# Digital_In-Out.net
KiCad netlist of a schematic drawn in Altium Designer
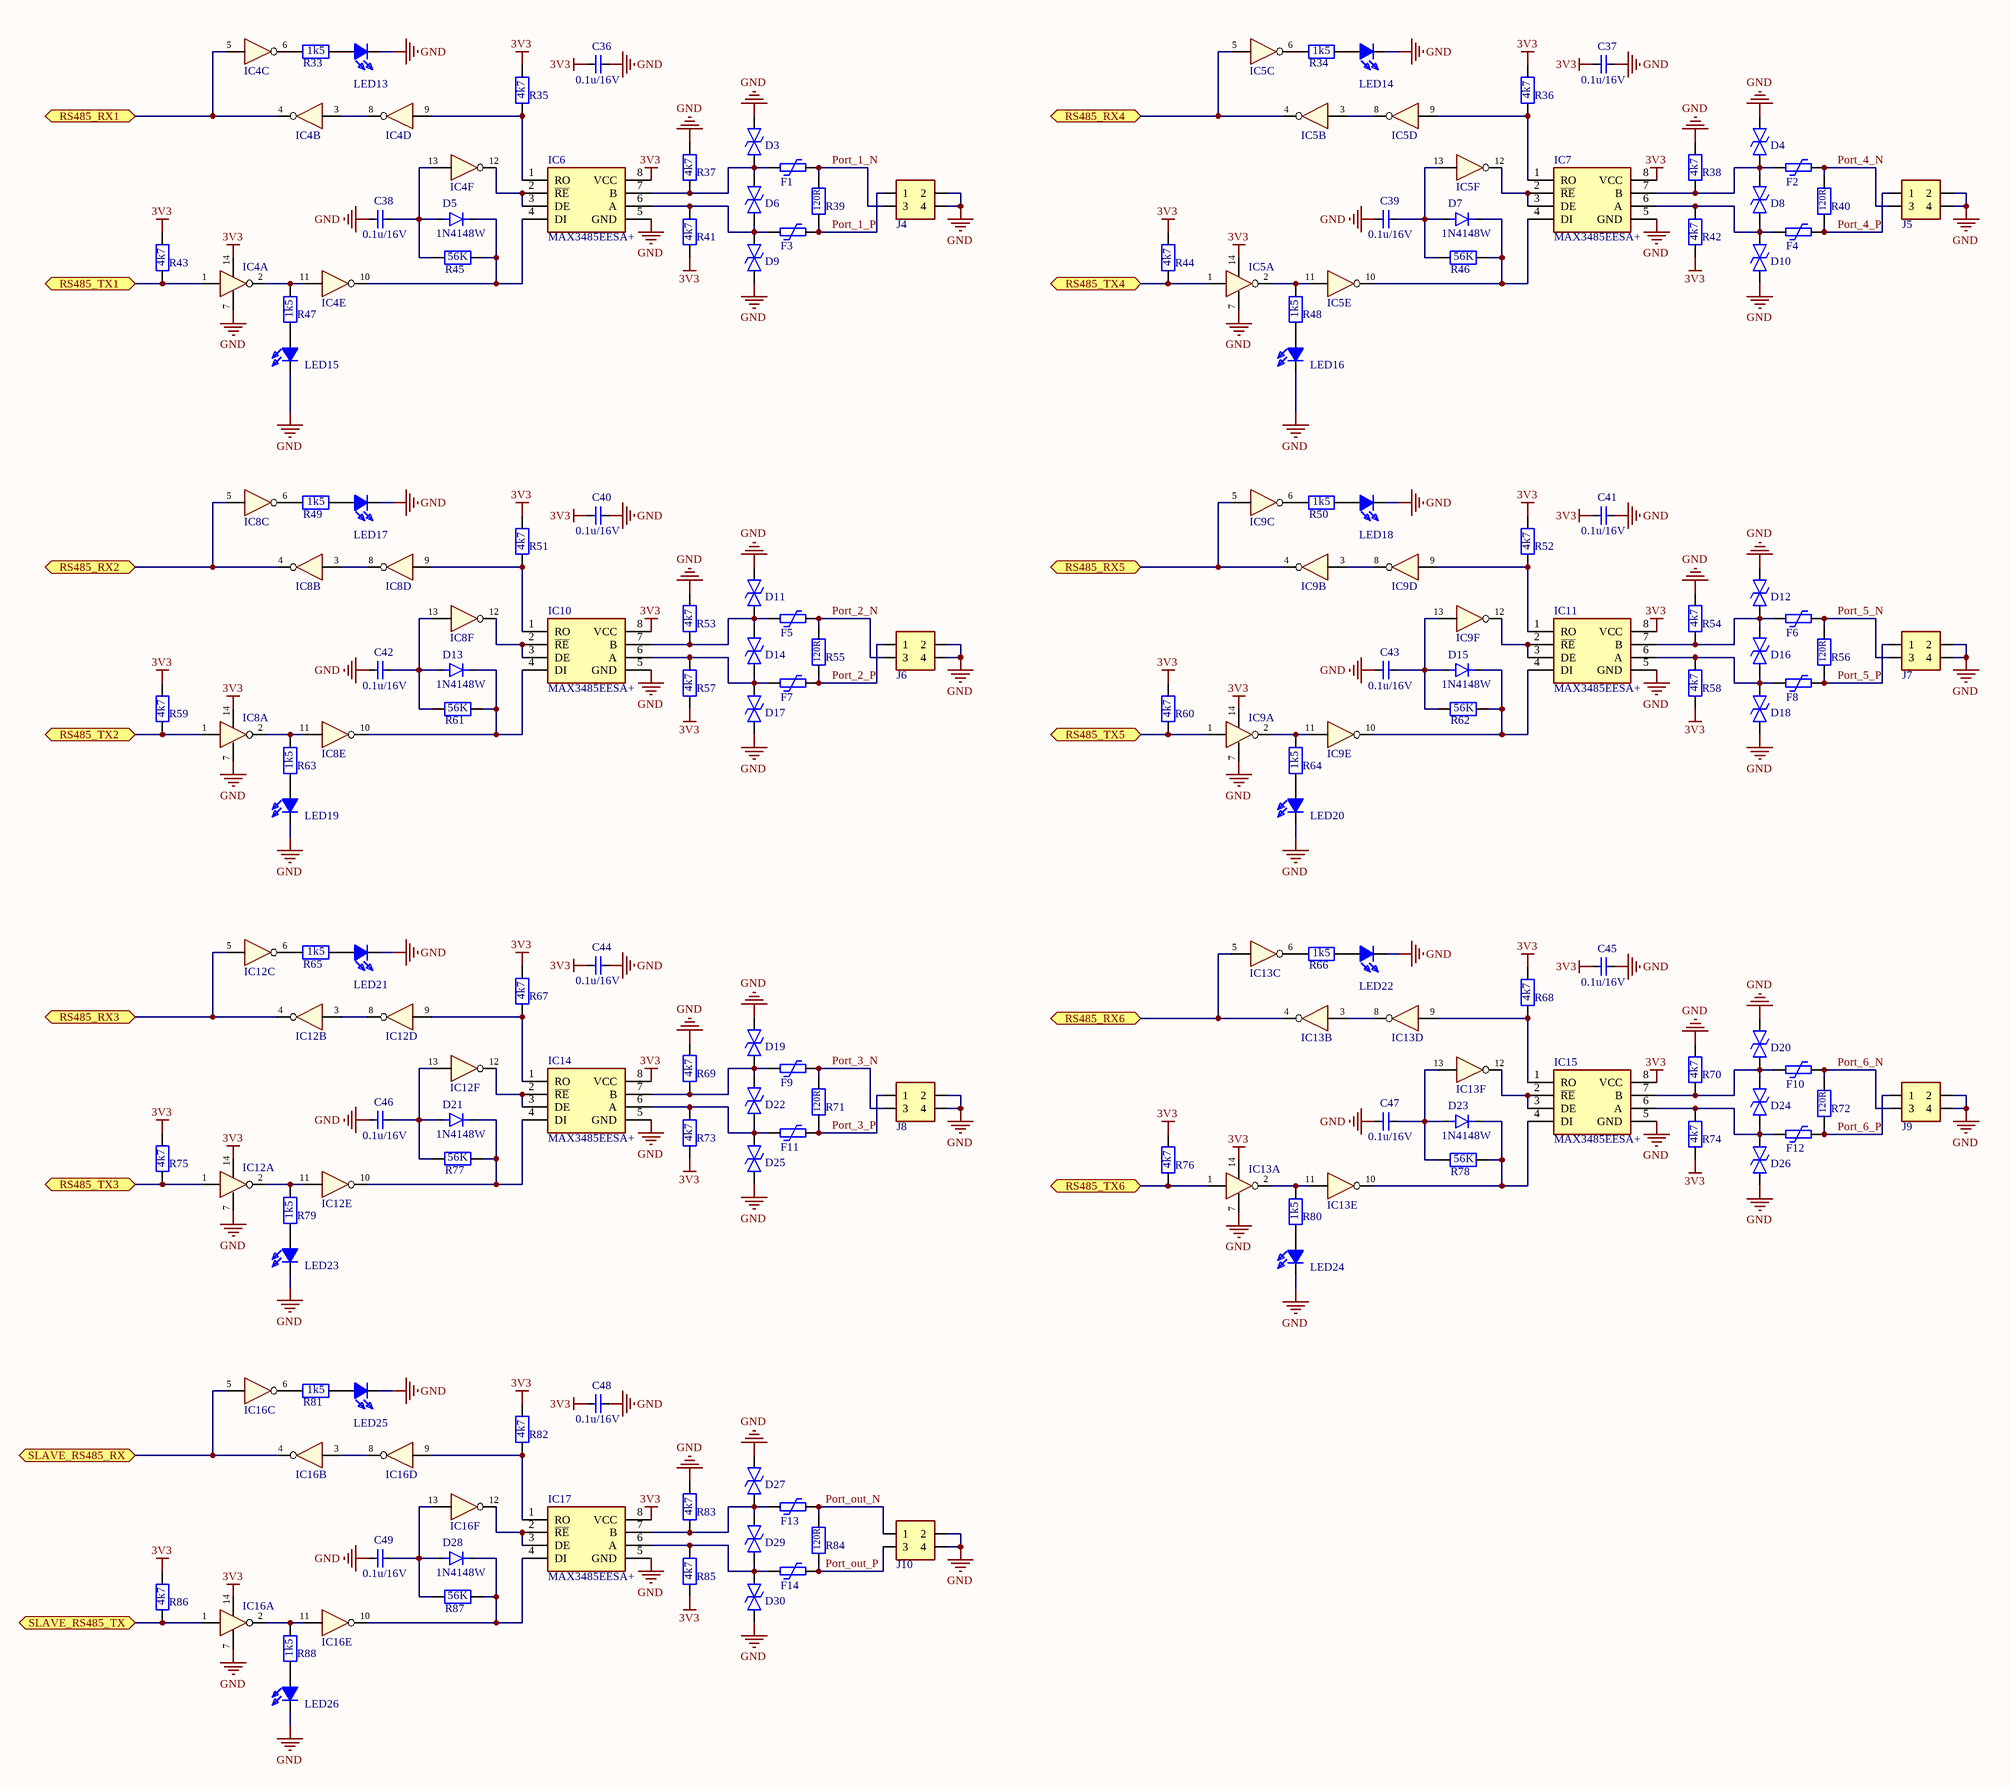
[diagram p0: Digital In-Out.SchDoc]

(export (version "E")
  (design (tool "Eeschema 10.0.6"))
  (components
    (comp (ref "C36")
      (value "0.1u/16V")
      (footprint "SamacSys:CAPC1608X95N")
      (description "Multilayer Ceramic Capacitors MLCC - SMD/SMT 16V 100pF C0G 0603 1%")
      (fields
        (field (name "MANUFACTURER_PART_NUMBER") "C0603C101F4GAC")
        (field (name "MOUSER PART NUMBER") "80-C0603C101F4G")
      )
      (libsource (lib "SamacSys") (part "Cap 0603 0.1u/16V"))
    )
    (comp (ref "C37")
      (value "0.1u/16V")
      (footprint "SamacSys:CAPC1608X95N")
      (description "Multilayer Ceramic Capacitors MLCC - SMD/SMT 16V 100pF C0G 0603 1%")
      (fields
        (field (name "MANUFACTURER_PART_NUMBER") "C0603C101F4GAC")
        (field (name "MOUSER PART NUMBER") "80-C0603C101F4G")
      )
      (libsource (lib "SamacSys") (part "Cap 0603 0.1u/16V"))
    )
    (comp (ref "C38")
      (value "0.1u/16V")
      (footprint "SamacSys:CAPC1608X95N")
      (description "Multilayer Ceramic Capacitors MLCC - SMD/SMT 16V 100pF C0G 0603 1%")
      (fields
        (field (name "MANUFACTURER_PART_NUMBER") "C0603C101F4GAC")
        (field (name "MOUSER PART NUMBER") "80-C0603C101F4G")
      )
      (libsource (lib "SamacSys") (part "Cap 0603 0.1u/16V"))
    )
    (comp (ref "C39")
      (value "0.1u/16V")
      (footprint "SamacSys:CAPC1608X95N")
      (description "Multilayer Ceramic Capacitors MLCC - SMD/SMT 16V 100pF C0G 0603 1%")
      (fields
        (field (name "MANUFACTURER_PART_NUMBER") "C0603C101F4GAC")
        (field (name "MOUSER PART NUMBER") "80-C0603C101F4G")
      )
      (libsource (lib "SamacSys") (part "Cap 0603 0.1u/16V"))
    )
    (comp (ref "C40")
      (value "0.1u/16V")
      (footprint "SamacSys:CAPC1608X95N")
      (description "Multilayer Ceramic Capacitors MLCC - SMD/SMT 16V 100pF C0G 0603 1%")
      (fields
        (field (name "MANUFACTURER_PART_NUMBER") "C0603C101F4GAC")
        (field (name "MOUSER PART NUMBER") "80-C0603C101F4G")
      )
      (libsource (lib "SamacSys") (part "Cap 0603 0.1u/16V"))
    )
    (comp (ref "C41")
      (value "0.1u/16V")
      (footprint "SamacSys:CAPC1608X95N")
      (description "Multilayer Ceramic Capacitors MLCC - SMD/SMT 16V 100pF C0G 0603 1%")
      (fields
        (field (name "MANUFACTURER_PART_NUMBER") "C0603C101F4GAC")
        (field (name "MOUSER PART NUMBER") "80-C0603C101F4G")
      )
      (libsource (lib "SamacSys") (part "Cap 0603 0.1u/16V"))
    )
    (comp (ref "C42")
      (value "0.1u/16V")
      (footprint "SamacSys:CAPC1608X95N")
      (description "Multilayer Ceramic Capacitors MLCC - SMD/SMT 16V 100pF C0G 0603 1%")
      (fields
        (field (name "MANUFACTURER_PART_NUMBER") "C0603C101F4GAC")
        (field (name "MOUSER PART NUMBER") "80-C0603C101F4G")
      )
      (libsource (lib "SamacSys") (part "Cap 0603 0.1u/16V"))
    )
    (comp (ref "C43")
      (value "0.1u/16V")
      (footprint "SamacSys:CAPC1608X95N")
      (description "Multilayer Ceramic Capacitors MLCC - SMD/SMT 16V 100pF C0G 0603 1%")
      (fields
        (field (name "MANUFACTURER_PART_NUMBER") "C0603C101F4GAC")
        (field (name "MOUSER PART NUMBER") "80-C0603C101F4G")
      )
      (libsource (lib "SamacSys") (part "Cap 0603 0.1u/16V"))
    )
    (comp (ref "C44")
      (value "0.1u/16V")
      (footprint "SamacSys:CAPC1608X95N")
      (description "Multilayer Ceramic Capacitors MLCC - SMD/SMT 16V 100pF C0G 0603 1%")
      (fields
        (field (name "MANUFACTURER_PART_NUMBER") "C0603C101F4GAC")
        (field (name "MOUSER PART NUMBER") "80-C0603C101F4G")
      )
      (libsource (lib "SamacSys") (part "Cap 0603 0.1u/16V"))
    )
    (comp (ref "C45")
      (value "0.1u/16V")
      (footprint "SamacSys:CAPC1608X95N")
      (description "Multilayer Ceramic Capacitors MLCC - SMD/SMT 16V 100pF C0G 0603 1%")
      (fields
        (field (name "MANUFACTURER_PART_NUMBER") "C0603C101F4GAC")
        (field (name "MOUSER PART NUMBER") "80-C0603C101F4G")
      )
      (libsource (lib "SamacSys") (part "Cap 0603 0.1u/16V"))
    )
    (comp (ref "C46")
      (value "0.1u/16V")
      (footprint "SamacSys:CAPC1608X95N")
      (description "Multilayer Ceramic Capacitors MLCC - SMD/SMT 16V 100pF C0G 0603 1%")
      (fields
        (field (name "MANUFACTURER_PART_NUMBER") "C0603C101F4GAC")
        (field (name "MOUSER PART NUMBER") "80-C0603C101F4G")
      )
      (libsource (lib "SamacSys") (part "Cap 0603 0.1u/16V"))
    )
    (comp (ref "C47")
      (value "0.1u/16V")
      (footprint "SamacSys:CAPC1608X95N")
      (description "Multilayer Ceramic Capacitors MLCC - SMD/SMT 16V 100pF C0G 0603 1%")
      (fields
        (field (name "MANUFACTURER_PART_NUMBER") "C0603C101F4GAC")
        (field (name "MOUSER PART NUMBER") "80-C0603C101F4G")
      )
      (libsource (lib "SamacSys") (part "Cap 0603 0.1u/16V"))
    )
    (comp (ref "C48")
      (value "0.1u/16V")
      (footprint "SamacSys:CAPC1608X95N")
      (description "Multilayer Ceramic Capacitors MLCC - SMD/SMT 16V 100pF C0G 0603 1%")
      (fields
        (field (name "MANUFACTURER_PART_NUMBER") "C0603C101F4GAC")
        (field (name "MOUSER PART NUMBER") "80-C0603C101F4G")
      )
      (libsource (lib "SamacSys") (part "Cap 0603 0.1u/16V"))
    )
    (comp (ref "C49")
      (value "0.1u/16V")
      (footprint "SamacSys:CAPC1608X95N")
      (description "Multilayer Ceramic Capacitors MLCC - SMD/SMT 16V 100pF C0G 0603 1%")
      (fields
        (field (name "MANUFACTURER_PART_NUMBER") "C0603C101F4GAC")
        (field (name "MOUSER PART NUMBER") "80-C0603C101F4G")
      )
      (libsource (lib "SamacSys") (part "Cap 0603 0.1u/16V"))
    )
    (comp (ref "D3")
      (value "SMAJ6.8CA")
      (footprint "SamacSys:DIOM5226X247N")
      (description "TVS Diode (Bi-directional) - 400W 10.5V 38.1A 5.8V 6.45VSMA(D")
      (libsource (lib "SamacSys") (part "SMAJ6.8CA"))
    )
    (comp (ref "D4")
      (value "SMAJ6.8CA")
      (footprint "SamacSys:DIOM5226X247N")
      (description "TVS Diode (Bi-directional) - 400W 10.5V 38.1A 5.8V 6.45VSMA(D")
      (libsource (lib "SamacSys") (part "SMAJ6.8CA"))
    )
    (comp (ref "D5")
      (value "1N4148W")
      (footprint "SamacSys:SOD3716X135N")
      (description "Diode")
      (fields
        (field (name "MANUFACTURER_PART_NUMBER") "1N4148W-E3-08")
        (field (name "MOUSER PART NUMBER") "78-1N4148W-E3-08")
      )
      (libsource (lib "SamacSys") (part "1N4148W"))
    )
    (comp (ref "D6")
      (value "SMAJ6.8CA")
      (footprint "SamacSys:DIOM5226X247N")
      (description "TVS Diode (Bi-directional) - 400W 10.5V 38.1A 5.8V 6.45VSMA(D")
      (libsource (lib "SamacSys") (part "SMAJ6.8CA"))
    )
    (comp (ref "D7")
      (value "1N4148W")
      (footprint "SamacSys:SOD3716X135N")
      (description "Diode")
      (fields
        (field (name "MANUFACTURER_PART_NUMBER") "1N4148W-E3-08")
        (field (name "MOUSER PART NUMBER") "78-1N4148W-E3-08")
      )
      (libsource (lib "SamacSys") (part "1N4148W"))
    )
    (comp (ref "D8")
      (value "SMAJ6.8CA")
      (footprint "SamacSys:DIOM5226X247N")
      (description "TVS Diode (Bi-directional) - 400W 10.5V 38.1A 5.8V 6.45VSMA(D")
      (libsource (lib "SamacSys") (part "SMAJ6.8CA"))
    )
    (comp (ref "D9")
      (value "SMAJ6.8CA")
      (footprint "SamacSys:DIOM5226X247N")
      (description "TVS Diode (Bi-directional) - 400W 10.5V 38.1A 5.8V 6.45VSMA(D")
      (libsource (lib "SamacSys") (part "SMAJ6.8CA"))
    )
    (comp (ref "D10")
      (value "SMAJ6.8CA")
      (footprint "SamacSys:DIOM5226X247N")
      (description "TVS Diode (Bi-directional) - 400W 10.5V 38.1A 5.8V 6.45VSMA(D")
      (libsource (lib "SamacSys") (part "SMAJ6.8CA"))
    )
    (comp (ref "D11")
      (value "SMAJ6.8CA")
      (footprint "SamacSys:DIOM5226X247N")
      (description "TVS Diode (Bi-directional) - 400W 10.5V 38.1A 5.8V 6.45VSMA(D")
      (libsource (lib "SamacSys") (part "SMAJ6.8CA"))
    )
    (comp (ref "D12")
      (value "SMAJ6.8CA")
      (footprint "SamacSys:DIOM5226X247N")
      (description "TVS Diode (Bi-directional) - 400W 10.5V 38.1A 5.8V 6.45VSMA(D")
      (libsource (lib "SamacSys") (part "SMAJ6.8CA"))
    )
    (comp (ref "D13")
      (value "1N4148W")
      (footprint "SamacSys:SOD3716X135N")
      (description "Diode")
      (fields
        (field (name "MANUFACTURER_PART_NUMBER") "1N4148W-E3-08")
        (field (name "MOUSER PART NUMBER") "78-1N4148W-E3-08")
      )
      (libsource (lib "SamacSys") (part "1N4148W"))
    )
    (comp (ref "D14")
      (value "SMAJ6.8CA")
      (footprint "SamacSys:DIOM5226X247N")
      (description "TVS Diode (Bi-directional) - 400W 10.5V 38.1A 5.8V 6.45VSMA(D")
      (libsource (lib "SamacSys") (part "SMAJ6.8CA"))
    )
    (comp (ref "D15")
      (value "1N4148W")
      (footprint "SamacSys:SOD3716X135N")
      (description "Diode")
      (fields
        (field (name "MANUFACTURER_PART_NUMBER") "1N4148W-E3-08")
        (field (name "MOUSER PART NUMBER") "78-1N4148W-E3-08")
      )
      (libsource (lib "SamacSys") (part "1N4148W"))
    )
    (comp (ref "D16")
      (value "SMAJ6.8CA")
      (footprint "SamacSys:DIOM5226X247N")
      (description "TVS Diode (Bi-directional) - 400W 10.5V 38.1A 5.8V 6.45VSMA(D")
      (libsource (lib "SamacSys") (part "SMAJ6.8CA"))
    )
    (comp (ref "D17")
      (value "SMAJ6.8CA")
      (footprint "SamacSys:DIOM5226X247N")
      (description "TVS Diode (Bi-directional) - 400W 10.5V 38.1A 5.8V 6.45VSMA(D")
      (libsource (lib "SamacSys") (part "SMAJ6.8CA"))
    )
    (comp (ref "D18")
      (value "SMAJ6.8CA")
      (footprint "SamacSys:DIOM5226X247N")
      (description "TVS Diode (Bi-directional) - 400W 10.5V 38.1A 5.8V 6.45VSMA(D")
      (libsource (lib "SamacSys") (part "SMAJ6.8CA"))
    )
    (comp (ref "D19")
      (value "SMAJ6.8CA")
      (footprint "SamacSys:DIOM5226X247N")
      (description "TVS Diode (Bi-directional) - 400W 10.5V 38.1A 5.8V 6.45VSMA(D")
      (libsource (lib "SamacSys") (part "SMAJ6.8CA"))
    )
    (comp (ref "D20")
      (value "SMAJ6.8CA")
      (footprint "SamacSys:DIOM5226X247N")
      (description "TVS Diode (Bi-directional) - 400W 10.5V 38.1A 5.8V 6.45VSMA(D")
      (libsource (lib "SamacSys") (part "SMAJ6.8CA"))
    )
    (comp (ref "D21")
      (value "1N4148W")
      (footprint "SamacSys:SOD3716X135N")
      (description "Diode")
      (fields
        (field (name "MANUFACTURER_PART_NUMBER") "1N4148W-E3-08")
        (field (name "MOUSER PART NUMBER") "78-1N4148W-E3-08")
      )
      (libsource (lib "SamacSys") (part "1N4148W"))
    )
    (comp (ref "D22")
      (value "SMAJ6.8CA")
      (footprint "SamacSys:DIOM5226X247N")
      (description "TVS Diode (Bi-directional) - 400W 10.5V 38.1A 5.8V 6.45VSMA(D")
      (libsource (lib "SamacSys") (part "SMAJ6.8CA"))
    )
    (comp (ref "D23")
      (value "1N4148W")
      (footprint "SamacSys:SOD3716X135N")
      (description "Diode")
      (fields
        (field (name "MANUFACTURER_PART_NUMBER") "1N4148W-E3-08")
        (field (name "MOUSER PART NUMBER") "78-1N4148W-E3-08")
      )
      (libsource (lib "SamacSys") (part "1N4148W"))
    )
    (comp (ref "D24")
      (value "SMAJ6.8CA")
      (footprint "SamacSys:DIOM5226X247N")
      (description "TVS Diode (Bi-directional) - 400W 10.5V 38.1A 5.8V 6.45VSMA(D")
      (libsource (lib "SamacSys") (part "SMAJ6.8CA"))
    )
    (comp (ref "D25")
      (value "SMAJ6.8CA")
      (footprint "SamacSys:DIOM5226X247N")
      (description "TVS Diode (Bi-directional) - 400W 10.5V 38.1A 5.8V 6.45VSMA(D")
      (libsource (lib "SamacSys") (part "SMAJ6.8CA"))
    )
    (comp (ref "D26")
      (value "SMAJ6.8CA")
      (footprint "SamacSys:DIOM5226X247N")
      (description "TVS Diode (Bi-directional) - 400W 10.5V 38.1A 5.8V 6.45VSMA(D")
      (libsource (lib "SamacSys") (part "SMAJ6.8CA"))
    )
    (comp (ref "D27")
      (value "SMAJ6.8CA")
      (footprint "SamacSys:DIOM5226X247N")
      (description "TVS Diode (Bi-directional) - 400W 10.5V 38.1A 5.8V 6.45VSMA(D")
      (libsource (lib "SamacSys") (part "SMAJ6.8CA"))
    )
    (comp (ref "D28")
      (value "1N4148W")
      (footprint "SamacSys:SOD3716X135N")
      (description "Diode")
      (fields
        (field (name "MANUFACTURER_PART_NUMBER") "1N4148W-E3-08")
        (field (name "MOUSER PART NUMBER") "78-1N4148W-E3-08")
      )
      (libsource (lib "SamacSys") (part "1N4148W"))
    )
    (comp (ref "D29")
      (value "SMAJ6.8CA")
      (footprint "SamacSys:DIOM5226X247N")
      (description "TVS Diode (Bi-directional) - 400W 10.5V 38.1A 5.8V 6.45VSMA(D")
      (libsource (lib "SamacSys") (part "SMAJ6.8CA"))
    )
    (comp (ref "D30")
      (value "SMAJ6.8CA")
      (footprint "SamacSys:DIOM5226X247N")
      (description "TVS Diode (Bi-directional) - 400W 10.5V 38.1A 5.8V 6.45VSMA(D")
      (libsource (lib "SamacSys") (part "SMAJ6.8CA"))
    )
    (comp (ref "F1")
      (value "USHT020KX")
      (footprint "MFUSHT020KX362")
      (description "Resettable Fuses - PPTC 1210 High Temp SMD Polymer PTC 0.20A/36V")
      (fields
        (field (name "MANUFACTURER_PART_NUMBER") "MF-USHT020KX/36-2")
        (field (name "MOUSER PART NUMBER") "652-MF-USHT020KX/36")
      )
      (libsource (lib "SamacSys") (part "USHT020KX"))
    )
    (comp (ref "F2")
      (value "USHT020KX")
      (footprint "MFUSHT020KX362")
      (description "Resettable Fuses - PPTC 1210 High Temp SMD Polymer PTC 0.20A/36V")
      (fields
        (field (name "MANUFACTURER_PART_NUMBER") "MF-USHT020KX/36-2")
        (field (name "MOUSER PART NUMBER") "652-MF-USHT020KX/36")
      )
      (libsource (lib "SamacSys") (part "USHT020KX"))
    )
    (comp (ref "F3")
      (value "USHT020KX")
      (footprint "MFUSHT020KX362")
      (description "Resettable Fuses - PPTC 1210 High Temp SMD Polymer PTC 0.20A/36V")
      (fields
        (field (name "MANUFACTURER_PART_NUMBER") "MF-USHT020KX/36-2")
        (field (name "MOUSER PART NUMBER") "652-MF-USHT020KX/36")
      )
      (libsource (lib "SamacSys") (part "USHT020KX"))
    )
    (comp (ref "F4")
      (value "USHT020KX")
      (footprint "MFUSHT020KX362")
      (description "Resettable Fuses - PPTC 1210 High Temp SMD Polymer PTC 0.20A/36V")
      (fields
        (field (name "MANUFACTURER_PART_NUMBER") "MF-USHT020KX/36-2")
        (field (name "MOUSER PART NUMBER") "652-MF-USHT020KX/36")
      )
      (libsource (lib "SamacSys") (part "USHT020KX"))
    )
    (comp (ref "F5")
      (value "USHT020KX")
      (footprint "MFUSHT020KX362")
      (description "Resettable Fuses - PPTC 1210 High Temp SMD Polymer PTC 0.20A/36V")
      (fields
        (field (name "MANUFACTURER_PART_NUMBER") "MF-USHT020KX/36-2")
        (field (name "MOUSER PART NUMBER") "652-MF-USHT020KX/36")
      )
      (libsource (lib "SamacSys") (part "USHT020KX"))
    )
    (comp (ref "F6")
      (value "USHT020KX")
      (footprint "MFUSHT020KX362")
      (description "Resettable Fuses - PPTC 1210 High Temp SMD Polymer PTC 0.20A/36V")
      (fields
        (field (name "MANUFACTURER_PART_NUMBER") "MF-USHT020KX/36-2")
        (field (name "MOUSER PART NUMBER") "652-MF-USHT020KX/36")
      )
      (libsource (lib "SamacSys") (part "USHT020KX"))
    )
    (comp (ref "F7")
      (value "USHT020KX")
      (footprint "MFUSHT020KX362")
      (description "Resettable Fuses - PPTC 1210 High Temp SMD Polymer PTC 0.20A/36V")
      (fields
        (field (name "MANUFACTURER_PART_NUMBER") "MF-USHT020KX/36-2")
        (field (name "MOUSER PART NUMBER") "652-MF-USHT020KX/36")
      )
      (libsource (lib "SamacSys") (part "USHT020KX"))
    )
    (comp (ref "F8")
      (value "USHT020KX")
      (footprint "MFUSHT020KX362")
      (description "Resettable Fuses - PPTC 1210 High Temp SMD Polymer PTC 0.20A/36V")
      (fields
        (field (name "MANUFACTURER_PART_NUMBER") "MF-USHT020KX/36-2")
        (field (name "MOUSER PART NUMBER") "652-MF-USHT020KX/36")
      )
      (libsource (lib "SamacSys") (part "USHT020KX"))
    )
    (comp (ref "F9")
      (value "USHT020KX")
      (footprint "MFUSHT020KX362")
      (description "Resettable Fuses - PPTC 1210 High Temp SMD Polymer PTC 0.20A/36V")
      (fields
        (field (name "MANUFACTURER_PART_NUMBER") "MF-USHT020KX/36-2")
        (field (name "MOUSER PART NUMBER") "652-MF-USHT020KX/36")
      )
      (libsource (lib "SamacSys") (part "USHT020KX"))
    )
    (comp (ref "F10")
      (value "USHT020KX")
      (footprint "MFUSHT020KX362")
      (description "Resettable Fuses - PPTC 1210 High Temp SMD Polymer PTC 0.20A/36V")
      (fields
        (field (name "MANUFACTURER_PART_NUMBER") "MF-USHT020KX/36-2")
        (field (name "MOUSER PART NUMBER") "652-MF-USHT020KX/36")
      )
      (libsource (lib "SamacSys") (part "USHT020KX"))
    )
    (comp (ref "F11")
      (value "USHT020KX")
      (footprint "MFUSHT020KX362")
      (description "Resettable Fuses - PPTC 1210 High Temp SMD Polymer PTC 0.20A/36V")
      (fields
        (field (name "MANUFACTURER_PART_NUMBER") "MF-USHT020KX/36-2")
        (field (name "MOUSER PART NUMBER") "652-MF-USHT020KX/36")
      )
      (libsource (lib "SamacSys") (part "USHT020KX"))
    )
    (comp (ref "F12")
      (value "USHT020KX")
      (footprint "MFUSHT020KX362")
      (description "Resettable Fuses - PPTC 1210 High Temp SMD Polymer PTC 0.20A/36V")
      (fields
        (field (name "MANUFACTURER_PART_NUMBER") "MF-USHT020KX/36-2")
        (field (name "MOUSER PART NUMBER") "652-MF-USHT020KX/36")
      )
      (libsource (lib "SamacSys") (part "USHT020KX"))
    )
    (comp (ref "F13")
      (value "USHT020KX")
      (footprint "MFUSHT020KX362")
      (description "Resettable Fuses - PPTC 1210 High Temp SMD Polymer PTC 0.20A/36V")
      (fields
        (field (name "MANUFACTURER_PART_NUMBER") "MF-USHT020KX/36-2")
        (field (name "MOUSER PART NUMBER") "652-MF-USHT020KX/36")
      )
      (libsource (lib "SamacSys") (part "USHT020KX"))
    )
    (comp (ref "F14")
      (value "USHT020KX")
      (footprint "MFUSHT020KX362")
      (description "Resettable Fuses - PPTC 1210 High Temp SMD Polymer PTC 0.20A/36V")
      (fields
        (field (name "MANUFACTURER_PART_NUMBER") "MF-USHT020KX/36-2")
        (field (name "MOUSER PART NUMBER") "652-MF-USHT020KX/36")
      )
      (libsource (lib "SamacSys") (part "USHT020KX"))
    )
    (comp (ref "IC4")
      (value "nverters Hex A 595-CD4069UBMT")
      (footprint "SamacSys:SOIC127P600X175-14N")
      (description "Inverters Hex A 595-CD4069UBMT")
      (fields
        (field (name "MANUFACTURER_PART_NUMBER") "CD4069UBM")
        (field (name "MOUSER PART NUMBER") "595-CD4069UBM")
      )
      (libsource (lib "SamacSys") (part "CD4069UBM"))
    )
    (comp (ref "IC5")
      (value "nverters Hex A 595-CD4069UBMT")
      (footprint "SamacSys:SOIC127P600X175-14N")
      (description "Inverters Hex A 595-CD4069UBMT")
      (fields
        (field (name "MANUFACTURER_PART_NUMBER") "CD4069UBM")
        (field (name "MOUSER PART NUMBER") "595-CD4069UBM")
      )
      (libsource (lib "SamacSys") (part "CD4069UBM"))
    )
    (comp (ref "IC6")
      (value "MAX3485EESA+")
      (footprint "SamacSys:SOIC127P600X175-8N")
      (description "Integrated Circuit")
      (fields (field (name "MOUSER PART NUMBER") "700-MAX3485EESA"))
      (libsource (lib "SamacSys") (part "MAX3485EESA+"))
    )
    (comp (ref "IC7")
      (value "MAX3485EESA+")
      (footprint "SamacSys:SOIC127P600X175-8N")
      (description "Integrated Circuit")
      (fields (field (name "MOUSER PART NUMBER") "700-MAX3485EESA"))
      (libsource (lib "SamacSys") (part "MAX3485EESA+"))
    )
    (comp (ref "IC8")
      (value "nverters Hex A 595-CD4069UBMT")
      (footprint "SamacSys:SOIC127P600X175-14N")
      (description "Inverters Hex A 595-CD4069UBMT")
      (fields
        (field (name "MANUFACTURER_PART_NUMBER") "CD4069UBM")
        (field (name "MOUSER PART NUMBER") "595-CD4069UBM")
      )
      (libsource (lib "SamacSys") (part "CD4069UBM"))
    )
    (comp (ref "IC9")
      (value "nverters Hex A 595-CD4069UBMT")
      (footprint "SamacSys:SOIC127P600X175-14N")
      (description "Inverters Hex A 595-CD4069UBMT")
      (fields
        (field (name "MANUFACTURER_PART_NUMBER") "CD4069UBM")
        (field (name "MOUSER PART NUMBER") "595-CD4069UBM")
      )
      (libsource (lib "SamacSys") (part "CD4069UBM"))
    )
    (comp (ref "IC10")
      (value "MAX3485EESA+")
      (footprint "SamacSys:SOIC127P600X175-8N")
      (description "Integrated Circuit")
      (fields (field (name "MOUSER PART NUMBER") "700-MAX3485EESA"))
      (libsource (lib "SamacSys") (part "MAX3485EESA+"))
    )
    (comp (ref "IC11")
      (value "MAX3485EESA+")
      (footprint "SamacSys:SOIC127P600X175-8N")
      (description "Integrated Circuit")
      (fields (field (name "MOUSER PART NUMBER") "700-MAX3485EESA"))
      (libsource (lib "SamacSys") (part "MAX3485EESA+"))
    )
    (comp (ref "IC12")
      (value "nverters Hex A 595-CD4069UBMT")
      (footprint "SamacSys:SOIC127P600X175-14N")
      (description "Inverters Hex A 595-CD4069UBMT")
      (fields
        (field (name "MANUFACTURER_PART_NUMBER") "CD4069UBM")
        (field (name "MOUSER PART NUMBER") "595-CD4069UBM")
      )
      (libsource (lib "SamacSys") (part "CD4069UBM"))
    )
    (comp (ref "IC13")
      (value "nverters Hex A 595-CD4069UBMT")
      (footprint "SamacSys:SOIC127P600X175-14N")
      (description "Inverters Hex A 595-CD4069UBMT")
      (fields
        (field (name "MANUFACTURER_PART_NUMBER") "CD4069UBM")
        (field (name "MOUSER PART NUMBER") "595-CD4069UBM")
      )
      (libsource (lib "SamacSys") (part "CD4069UBM"))
    )
    (comp (ref "IC14")
      (value "MAX3485EESA+")
      (footprint "SamacSys:SOIC127P600X175-8N")
      (description "Integrated Circuit")
      (fields (field (name "MOUSER PART NUMBER") "700-MAX3485EESA"))
      (libsource (lib "SamacSys") (part "MAX3485EESA+"))
    )
    (comp (ref "IC15")
      (value "MAX3485EESA+")
      (footprint "SamacSys:SOIC127P600X175-8N")
      (description "Integrated Circuit")
      (fields (field (name "MOUSER PART NUMBER") "700-MAX3485EESA"))
      (libsource (lib "SamacSys") (part "MAX3485EESA+"))
    )
    (comp (ref "IC16")
      (value "nverters Hex A 595-CD4069UBMT")
      (footprint "SamacSys:SOIC127P600X175-14N")
      (description "Inverters Hex A 595-CD4069UBMT")
      (fields
        (field (name "MANUFACTURER_PART_NUMBER") "CD4069UBM")
        (field (name "MOUSER PART NUMBER") "595-CD4069UBM")
      )
      (libsource (lib "SamacSys") (part "CD4069UBM"))
    )
    (comp (ref "IC17")
      (value "MAX3485EESA+")
      (footprint "SamacSys:SOIC127P600X175-8N")
      (description "Integrated Circuit")
      (fields (field (name "MOUSER PART NUMBER") "700-MAX3485EESA"))
      (libsource (lib "SamacSys") (part "MAX3485EESA+"))
    )
    (comp (ref "J4")
      (value "Connector THD 4 position 0.165\" (4.20mm)")
      (footprint "SamacSys:RHDR4W125P550X420_2X2_960X960X1310P")
      (description "Connector Header Through Hole 4 position 0.165\" (4.20mm)")
      (fields (field (name "MANUFACTURER_PART_NUMBER") "0039281043"))
      (libsource (lib "SamacSys") (part "Connector 2x2"))
    )
    (comp (ref "J5")
      (value "Connector THD 4 position 0.165\" (4.20mm)")
      (footprint "SamacSys:RHDR4W125P550X420_2X2_960X960X1310P")
      (description "Connector Header Through Hole 4 position 0.165\" (4.20mm)")
      (fields (field (name "MANUFACTURER_PART_NUMBER") "0039281043"))
      (libsource (lib "SamacSys") (part "Connector 2x2"))
    )
    (comp (ref "J6")
      (value "Connector THD 4 position 0.165\" (4.20mm)")
      (footprint "SamacSys:RHDR4W125P550X420_2X2_960X960X1310P")
      (description "Connector Header Through Hole 4 position 0.165\" (4.20mm)")
      (fields (field (name "MANUFACTURER_PART_NUMBER") "0039281043"))
      (libsource (lib "SamacSys") (part "Connector 2x2"))
    )
    (comp (ref "J7")
      (value "Connector THD 4 position 0.165\" (4.20mm)")
      (footprint "SamacSys:RHDR4W125P550X420_2X2_960X960X1310P")
      (description "Connector Header Through Hole 4 position 0.165\" (4.20mm)")
      (fields (field (name "MANUFACTURER_PART_NUMBER") "0039281043"))
      (libsource (lib "SamacSys") (part "Connector 2x2"))
    )
    (comp (ref "J8")
      (value "Connector THD 4 position 0.165\" (4.20mm)")
      (footprint "SamacSys:RHDR4W125P550X420_2X2_960X960X1310P")
      (description "Connector Header Through Hole 4 position 0.165\" (4.20mm)")
      (fields (field (name "MANUFACTURER_PART_NUMBER") "0039281043"))
      (libsource (lib "SamacSys") (part "Connector 2x2"))
    )
    (comp (ref "J9")
      (value "Connector THD 4 position 0.165\" (4.20mm)")
      (footprint "SamacSys:RHDR4W125P550X420_2X2_960X960X1310P")
      (description "Connector Header Through Hole 4 position 0.165\" (4.20mm)")
      (fields (field (name "MANUFACTURER_PART_NUMBER") "0039281043"))
      (libsource (lib "SamacSys") (part "Connector 2x2"))
    )
    (comp (ref "J10")
      (value "Connector THD 4 position 0.165\" (4.20mm)")
      (footprint "SamacSys:RHDR4W125P550X420_2X2_960X960X1310P")
      (description "Connector Header Through Hole 4 position 0.165\" (4.20mm)")
      (fields (field (name "MANUFACTURER_PART_NUMBER") "0039281043"))
      (libsource (lib "SamacSys") (part "Connector 2x2"))
    )
    (comp (ref "LED13")
      (value "LED0603_BLUE")
      (footprint "SamacSys:LEDC1608X80N")
      (description "LED")
      (fields
        (field (name "MANUFACTURER_PART_NUMBER") "150060BS75000")
        (field (name "MOUSER PART NUMBER") "710-150060BS75000")
      )
      (libsource (lib "SamacSys") (part "LED0603_BLUE"))
    )
    (comp (ref "LED14")
      (value "LED0603_BLUE")
      (footprint "SamacSys:LEDC1608X80N")
      (description "LED")
      (fields
        (field (name "MANUFACTURER_PART_NUMBER") "150060BS75000")
        (field (name "MOUSER PART NUMBER") "710-150060BS75000")
      )
      (libsource (lib "SamacSys") (part "LED0603_BLUE"))
    )
    (comp (ref "LED15")
      (value "LED0603_BLUE")
      (footprint "SamacSys:LEDC1608X80N")
      (description "LED")
      (fields
        (field (name "MANUFACTURER_PART_NUMBER") "150060BS75000")
        (field (name "MOUSER PART NUMBER") "710-150060BS75000")
      )
      (libsource (lib "SamacSys") (part "LED0603_BLUE"))
    )
    (comp (ref "LED16")
      (value "LED0603_BLUE")
      (footprint "SamacSys:LEDC1608X80N")
      (description "LED")
      (fields
        (field (name "MANUFACTURER_PART_NUMBER") "150060BS75000")
        (field (name "MOUSER PART NUMBER") "710-150060BS75000")
      )
      (libsource (lib "SamacSys") (part "LED0603_BLUE"))
    )
    (comp (ref "LED17")
      (value "LED0603_BLUE")
      (footprint "SamacSys:LEDC1608X80N")
      (description "LED")
      (fields
        (field (name "MANUFACTURER_PART_NUMBER") "150060BS75000")
        (field (name "MOUSER PART NUMBER") "710-150060BS75000")
      )
      (libsource (lib "SamacSys") (part "LED0603_BLUE"))
    )
    (comp (ref "LED18")
      (value "LED0603_BLUE")
      (footprint "SamacSys:LEDC1608X80N")
      (description "LED")
      (fields
        (field (name "MANUFACTURER_PART_NUMBER") "150060BS75000")
        (field (name "MOUSER PART NUMBER") "710-150060BS75000")
      )
      (libsource (lib "SamacSys") (part "LED0603_BLUE"))
    )
    (comp (ref "LED19")
      (value "LED0603_BLUE")
      (footprint "SamacSys:LEDC1608X80N")
      (description "LED")
      (fields
        (field (name "MANUFACTURER_PART_NUMBER") "150060BS75000")
        (field (name "MOUSER PART NUMBER") "710-150060BS75000")
      )
      (libsource (lib "SamacSys") (part "LED0603_BLUE"))
    )
    (comp (ref "LED20")
      (value "LED0603_BLUE")
      (footprint "SamacSys:LEDC1608X80N")
      (description "LED")
      (fields
        (field (name "MANUFACTURER_PART_NUMBER") "150060BS75000")
        (field (name "MOUSER PART NUMBER") "710-150060BS75000")
      )
      (libsource (lib "SamacSys") (part "LED0603_BLUE"))
    )
    (comp (ref "LED21")
      (value "LED0603_BLUE")
      (footprint "SamacSys:LEDC1608X80N")
      (description "LED")
      (fields
        (field (name "MANUFACTURER_PART_NUMBER") "150060BS75000")
        (field (name "MOUSER PART NUMBER") "710-150060BS75000")
      )
      (libsource (lib "SamacSys") (part "LED0603_BLUE"))
    )
    (comp (ref "LED22")
      (value "LED0603_BLUE")
      (footprint "SamacSys:LEDC1608X80N")
      (description "LED")
      (fields
        (field (name "MANUFACTURER_PART_NUMBER") "150060BS75000")
        (field (name "MOUSER PART NUMBER") "710-150060BS75000")
      )
      (libsource (lib "SamacSys") (part "LED0603_BLUE"))
    )
    (comp (ref "LED23")
      (value "LED0603_BLUE")
      (footprint "SamacSys:LEDC1608X80N")
      (description "LED")
      (fields
        (field (name "MANUFACTURER_PART_NUMBER") "150060BS75000")
        (field (name "MOUSER PART NUMBER") "710-150060BS75000")
      )
      (libsource (lib "SamacSys") (part "LED0603_BLUE"))
    )
    (comp (ref "LED24")
      (value "LED0603_BLUE")
      (footprint "SamacSys:LEDC1608X80N")
      (description "LED")
      (fields
        (field (name "MANUFACTURER_PART_NUMBER") "150060BS75000")
        (field (name "MOUSER PART NUMBER") "710-150060BS75000")
      )
      (libsource (lib "SamacSys") (part "LED0603_BLUE"))
    )
    (comp (ref "LED25")
      (value "LED0603_BLUE")
      (footprint "SamacSys:LEDC1608X80N")
      (description "LED")
      (fields
        (field (name "MANUFACTURER_PART_NUMBER") "150060BS75000")
        (field (name "MOUSER PART NUMBER") "710-150060BS75000")
      )
      (libsource (lib "SamacSys") (part "LED0603_BLUE"))
    )
    (comp (ref "LED26")
      (value "LED0603_BLUE")
      (footprint "SamacSys:LEDC1608X80N")
      (description "LED")
      (fields
        (field (name "MANUFACTURER_PART_NUMBER") "150060BS75000")
        (field (name "MOUSER PART NUMBER") "710-150060BS75000")
      )
      (libsource (lib "SamacSys") (part "LED0603_BLUE"))
    )
    (comp (ref "R33")
      (value "Res 0603 1k5")
      (footprint "SamacSys:RESC1608X55N")
      (description "Thick Film Resistors - SMD 1.5 kOhms 100mW 0603 1%")
      (fields
        (field (name "MANUFACTURER_PART_NUMBER") "RC0603FR-071K5L")
        (field (name "MOUSER PART NUMBER") "603-RC0603FR-071K5L")
      )
      (libsource (lib "") (part "Res 0603 1k5_1"))
    )
    (comp (ref "R34")
      (value "Res 0603 1k5")
      (footprint "SamacSys:RESC1608X55N")
      (description "Thick Film Resistors - SMD 1.5 kOhms 100mW 0603 1%")
      (fields
        (field (name "MANUFACTURER_PART_NUMBER") "RC0603FR-071K5L")
        (field (name "MOUSER PART NUMBER") "603-RC0603FR-071K5L")
      )
      (libsource (lib "") (part "Res 0603 1k5_1"))
    )
    (comp (ref "R35")
      (value "Res 0603 4k7")
      (footprint "SamacSys:RESC1608X55N")
      (description "Thick Film Resistors - SMD 0603 4.7Kohms 0.2W 1% AEC-Q200")
      (fields
        (field (name "MANUFACTURER_PART_NUMBER") "ERJ-P03F4701V")
        (field (name "MOUSER PART NUMBER") "667-ERJ-P03F4701V")
      )
      (libsource (lib "SamacSys") (part "Res 0603 4k7"))
    )
    (comp (ref "R36")
      (value "Res 0603 4k7")
      (footprint "SamacSys:RESC1608X55N")
      (description "Thick Film Resistors - SMD 0603 4.7Kohms 0.2W 1% AEC-Q200")
      (fields
        (field (name "MANUFACTURER_PART_NUMBER") "ERJ-P03F4701V")
        (field (name "MOUSER PART NUMBER") "667-ERJ-P03F4701V")
      )
      (libsource (lib "SamacSys") (part "Res 0603 4k7"))
    )
    (comp (ref "R37")
      (value "Res 0603 4k7")
      (footprint "SamacSys:RESC1608X55N")
      (description "Thick Film Resistors - SMD 0603 4.7Kohms 0.2W 1% AEC-Q200")
      (fields
        (field (name "MANUFACTURER_PART_NUMBER") "ERJ-P03F4701V")
        (field (name "MOUSER PART NUMBER") "667-ERJ-P03F4701V")
      )
      (libsource (lib "SamacSys") (part "Res 0603 4k7"))
    )
    (comp (ref "R38")
      (value "Res 0603 4k7")
      (footprint "SamacSys:RESC1608X55N")
      (description "Thick Film Resistors - SMD 0603 4.7Kohms 0.2W 1% AEC-Q200")
      (fields
        (field (name "MANUFACTURER_PART_NUMBER") "ERJ-P03F4701V")
        (field (name "MOUSER PART NUMBER") "667-ERJ-P03F4701V")
      )
      (libsource (lib "SamacSys") (part "Res 0603 4k7"))
    )
    (comp (ref "R39")
      (value "120R")
      (footprint "SamacSys:RESC1608X55N")
      (description "Thick Film Resistors - SMD 0603 120ohms 1% AEC-Q200")
      (fields
        (field (name "MANUFACTURER_PART_NUMBER") "ERJ-3EKF1200V")
        (field (name "MOUSER PART NUMBER") "667-ERJ-3EKF1200V")
      )
      (libsource (lib "SamacSys") (part "Res 0603 120R"))
    )
    (comp (ref "R40")
      (value "120R")
      (footprint "SamacSys:RESC1608X55N")
      (description "Thick Film Resistors - SMD 0603 120ohms 1% AEC-Q200")
      (fields
        (field (name "MANUFACTURER_PART_NUMBER") "ERJ-3EKF1200V")
        (field (name "MOUSER PART NUMBER") "667-ERJ-3EKF1200V")
      )
      (libsource (lib "SamacSys") (part "Res 0603 120R"))
    )
    (comp (ref "R41")
      (value "Res 0603 4k7")
      (footprint "SamacSys:RESC1608X55N")
      (description "Thick Film Resistors - SMD 0603 4.7Kohms 0.2W 1% AEC-Q200")
      (fields
        (field (name "MANUFACTURER_PART_NUMBER") "ERJ-P03F4701V")
        (field (name "MOUSER PART NUMBER") "667-ERJ-P03F4701V")
      )
      (libsource (lib "SamacSys") (part "Res 0603 4k7"))
    )
    (comp (ref "R42")
      (value "Res 0603 4k7")
      (footprint "SamacSys:RESC1608X55N")
      (description "Thick Film Resistors - SMD 0603 4.7Kohms 0.2W 1% AEC-Q200")
      (fields
        (field (name "MANUFACTURER_PART_NUMBER") "ERJ-P03F4701V")
        (field (name "MOUSER PART NUMBER") "667-ERJ-P03F4701V")
      )
      (libsource (lib "SamacSys") (part "Res 0603 4k7"))
    )
    (comp (ref "R43")
      (value "Res 0603 4k7")
      (footprint "SamacSys:RESC1608X55N")
      (description "Thick Film Resistors - SMD 0603 4.7Kohms 0.2W 1% AEC-Q200")
      (fields
        (field (name "MANUFACTURER_PART_NUMBER") "ERJ-P03F4701V")
        (field (name "MOUSER PART NUMBER") "667-ERJ-P03F4701V")
      )
      (libsource (lib "SamacSys") (part "Res 0603 4k7"))
    )
    (comp (ref "R44")
      (value "Res 0603 4k7")
      (footprint "SamacSys:RESC1608X55N")
      (description "Thick Film Resistors - SMD 0603 4.7Kohms 0.2W 1% AEC-Q200")
      (fields
        (field (name "MANUFACTURER_PART_NUMBER") "ERJ-P03F4701V")
        (field (name "MOUSER PART NUMBER") "667-ERJ-P03F4701V")
      )
      (libsource (lib "SamacSys") (part "Res 0603 4k7"))
    )
    (comp (ref "R45")
      (value "56k")
      (footprint "SamacSys:RESC1608X55N")
      (description "Thick Film Resistors - SMD 0603 56Kohms 1% AEC-Q200")
      (fields
        (field (name "MANUFACTURER_PART_NUMBER") "ERJ-3EKF5602V")
        (field (name "MOUSER PART NUMBER") "667-ERJ-3EKF5602V")
      )
      (libsource (lib "SamacSys") (part "Res 0603 56k"))
    )
    (comp (ref "R46")
      (value "56k")
      (footprint "SamacSys:RESC1608X55N")
      (description "Thick Film Resistors - SMD 0603 56Kohms 1% AEC-Q200")
      (fields
        (field (name "MANUFACTURER_PART_NUMBER") "ERJ-3EKF5602V")
        (field (name "MOUSER PART NUMBER") "667-ERJ-3EKF5602V")
      )
      (libsource (lib "SamacSys") (part "Res 0603 56k"))
    )
    (comp (ref "R47")
      (value "Res 0603 1k5")
      (footprint "SamacSys:RESC1608X55N")
      (description "Thick Film Resistors - SMD 1.5 kOhms 100mW 0603 1%")
      (fields
        (field (name "MANUFACTURER_PART_NUMBER") "RC0603FR-071K5L")
        (field (name "MOUSER PART NUMBER") "603-RC0603FR-071K5L")
      )
      (libsource (lib "SamacSys") (part "Res 0603 1k5"))
    )
    (comp (ref "R48")
      (value "Res 0603 1k5")
      (footprint "SamacSys:RESC1608X55N")
      (description "Thick Film Resistors - SMD 1.5 kOhms 100mW 0603 1%")
      (fields
        (field (name "MANUFACTURER_PART_NUMBER") "RC0603FR-071K5L")
        (field (name "MOUSER PART NUMBER") "603-RC0603FR-071K5L")
      )
      (libsource (lib "SamacSys") (part "Res 0603 1k5"))
    )
    (comp (ref "R49")
      (value "Res 0603 1k5")
      (footprint "SamacSys:RESC1608X55N")
      (description "Thick Film Resistors - SMD 1.5 kOhms 100mW 0603 1%")
      (fields
        (field (name "MANUFACTURER_PART_NUMBER") "RC0603FR-071K5L")
        (field (name "MOUSER PART NUMBER") "603-RC0603FR-071K5L")
      )
      (libsource (lib "") (part "Res 0603 1k5_1"))
    )
    (comp (ref "R50")
      (value "Res 0603 1k5")
      (footprint "SamacSys:RESC1608X55N")
      (description "Thick Film Resistors - SMD 1.5 kOhms 100mW 0603 1%")
      (fields
        (field (name "MANUFACTURER_PART_NUMBER") "RC0603FR-071K5L")
        (field (name "MOUSER PART NUMBER") "603-RC0603FR-071K5L")
      )
      (libsource (lib "") (part "Res 0603 1k5_1"))
    )
    (comp (ref "R51")
      (value "Res 0603 4k7")
      (footprint "SamacSys:RESC1608X55N")
      (description "Thick Film Resistors - SMD 0603 4.7Kohms 0.2W 1% AEC-Q200")
      (fields
        (field (name "MANUFACTURER_PART_NUMBER") "ERJ-P03F4701V")
        (field (name "MOUSER PART NUMBER") "667-ERJ-P03F4701V")
      )
      (libsource (lib "SamacSys") (part "Res 0603 4k7"))
    )
    (comp (ref "R52")
      (value "Res 0603 4k7")
      (footprint "SamacSys:RESC1608X55N")
      (description "Thick Film Resistors - SMD 0603 4.7Kohms 0.2W 1% AEC-Q200")
      (fields
        (field (name "MANUFACTURER_PART_NUMBER") "ERJ-P03F4701V")
        (field (name "MOUSER PART NUMBER") "667-ERJ-P03F4701V")
      )
      (libsource (lib "SamacSys") (part "Res 0603 4k7"))
    )
    (comp (ref "R53")
      (value "Res 0603 4k7")
      (footprint "SamacSys:RESC1608X55N")
      (description "Thick Film Resistors - SMD 0603 4.7Kohms 0.2W 1% AEC-Q200")
      (fields
        (field (name "MANUFACTURER_PART_NUMBER") "ERJ-P03F4701V")
        (field (name "MOUSER PART NUMBER") "667-ERJ-P03F4701V")
      )
      (libsource (lib "SamacSys") (part "Res 0603 4k7"))
    )
    (comp (ref "R54")
      (value "Res 0603 4k7")
      (footprint "SamacSys:RESC1608X55N")
      (description "Thick Film Resistors - SMD 0603 4.7Kohms 0.2W 1% AEC-Q200")
      (fields
        (field (name "MANUFACTURER_PART_NUMBER") "ERJ-P03F4701V")
        (field (name "MOUSER PART NUMBER") "667-ERJ-P03F4701V")
      )
      (libsource (lib "SamacSys") (part "Res 0603 4k7"))
    )
    (comp (ref "R55")
      (value "120R")
      (footprint "SamacSys:RESC1608X55N")
      (description "Thick Film Resistors - SMD 0603 120ohms 1% AEC-Q200")
      (fields
        (field (name "MANUFACTURER_PART_NUMBER") "ERJ-3EKF1200V")
        (field (name "MOUSER PART NUMBER") "667-ERJ-3EKF1200V")
      )
      (libsource (lib "SamacSys") (part "Res 0603 120R"))
    )
    (comp (ref "R56")
      (value "120R")
      (footprint "SamacSys:RESC1608X55N")
      (description "Thick Film Resistors - SMD 0603 120ohms 1% AEC-Q200")
      (fields
        (field (name "MANUFACTURER_PART_NUMBER") "ERJ-3EKF1200V")
        (field (name "MOUSER PART NUMBER") "667-ERJ-3EKF1200V")
      )
      (libsource (lib "SamacSys") (part "Res 0603 120R"))
    )
    (comp (ref "R57")
      (value "Res 0603 4k7")
      (footprint "SamacSys:RESC1608X55N")
      (description "Thick Film Resistors - SMD 0603 4.7Kohms 0.2W 1% AEC-Q200")
      (fields
        (field (name "MANUFACTURER_PART_NUMBER") "ERJ-P03F4701V")
        (field (name "MOUSER PART NUMBER") "667-ERJ-P03F4701V")
      )
      (libsource (lib "SamacSys") (part "Res 0603 4k7"))
    )
    (comp (ref "R58")
      (value "Res 0603 4k7")
      (footprint "SamacSys:RESC1608X55N")
      (description "Thick Film Resistors - SMD 0603 4.7Kohms 0.2W 1% AEC-Q200")
      (fields
        (field (name "MANUFACTURER_PART_NUMBER") "ERJ-P03F4701V")
        (field (name "MOUSER PART NUMBER") "667-ERJ-P03F4701V")
      )
      (libsource (lib "SamacSys") (part "Res 0603 4k7"))
    )
    (comp (ref "R59")
      (value "Res 0603 4k7")
      (footprint "SamacSys:RESC1608X55N")
      (description "Thick Film Resistors - SMD 0603 4.7Kohms 0.2W 1% AEC-Q200")
      (fields
        (field (name "MANUFACTURER_PART_NUMBER") "ERJ-P03F4701V")
        (field (name "MOUSER PART NUMBER") "667-ERJ-P03F4701V")
      )
      (libsource (lib "SamacSys") (part "Res 0603 4k7"))
    )
    (comp (ref "R60")
      (value "Res 0603 4k7")
      (footprint "SamacSys:RESC1608X55N")
      (description "Thick Film Resistors - SMD 0603 4.7Kohms 0.2W 1% AEC-Q200")
      (fields
        (field (name "MANUFACTURER_PART_NUMBER") "ERJ-P03F4701V")
        (field (name "MOUSER PART NUMBER") "667-ERJ-P03F4701V")
      )
      (libsource (lib "SamacSys") (part "Res 0603 4k7"))
    )
    (comp (ref "R61")
      (value "56k")
      (footprint "SamacSys:RESC1608X55N")
      (description "Thick Film Resistors - SMD 0603 56Kohms 1% AEC-Q200")
      (fields
        (field (name "MANUFACTURER_PART_NUMBER") "ERJ-3EKF5602V")
        (field (name "MOUSER PART NUMBER") "667-ERJ-3EKF5602V")
      )
      (libsource (lib "SamacSys") (part "Res 0603 56k"))
    )
    (comp (ref "R62")
      (value "56k")
      (footprint "SamacSys:RESC1608X55N")
      (description "Thick Film Resistors - SMD 0603 56Kohms 1% AEC-Q200")
      (fields
        (field (name "MANUFACTURER_PART_NUMBER") "ERJ-3EKF5602V")
        (field (name "MOUSER PART NUMBER") "667-ERJ-3EKF5602V")
      )
      (libsource (lib "SamacSys") (part "Res 0603 56k"))
    )
    (comp (ref "R63")
      (value "Res 0603 1k5")
      (footprint "SamacSys:RESC1608X55N")
      (description "Thick Film Resistors - SMD 1.5 kOhms 100mW 0603 1%")
      (fields
        (field (name "MANUFACTURER_PART_NUMBER") "RC0603FR-071K5L")
        (field (name "MOUSER PART NUMBER") "603-RC0603FR-071K5L")
      )
      (libsource (lib "SamacSys") (part "Res 0603 1k5"))
    )
    (comp (ref "R64")
      (value "Res 0603 1k5")
      (footprint "SamacSys:RESC1608X55N")
      (description "Thick Film Resistors - SMD 1.5 kOhms 100mW 0603 1%")
      (fields
        (field (name "MANUFACTURER_PART_NUMBER") "RC0603FR-071K5L")
        (field (name "MOUSER PART NUMBER") "603-RC0603FR-071K5L")
      )
      (libsource (lib "SamacSys") (part "Res 0603 1k5"))
    )
    (comp (ref "R65")
      (value "Res 0603 1k5")
      (footprint "SamacSys:RESC1608X55N")
      (description "Thick Film Resistors - SMD 1.5 kOhms 100mW 0603 1%")
      (fields
        (field (name "MANUFACTURER_PART_NUMBER") "RC0603FR-071K5L")
        (field (name "MOUSER PART NUMBER") "603-RC0603FR-071K5L")
      )
      (libsource (lib "") (part "Res 0603 1k5_1"))
    )
    (comp (ref "R66")
      (value "Res 0603 1k5")
      (footprint "SamacSys:RESC1608X55N")
      (description "Thick Film Resistors - SMD 1.5 kOhms 100mW 0603 1%")
      (fields
        (field (name "MANUFACTURER_PART_NUMBER") "RC0603FR-071K5L")
        (field (name "MOUSER PART NUMBER") "603-RC0603FR-071K5L")
      )
      (libsource (lib "") (part "Res 0603 1k5_1"))
    )
    (comp (ref "R67")
      (value "Res 0603 4k7")
      (footprint "SamacSys:RESC1608X55N")
      (description "Thick Film Resistors - SMD 0603 4.7Kohms 0.2W 1% AEC-Q200")
      (fields
        (field (name "MANUFACTURER_PART_NUMBER") "ERJ-P03F4701V")
        (field (name "MOUSER PART NUMBER") "667-ERJ-P03F4701V")
      )
      (libsource (lib "SamacSys") (part "Res 0603 4k7"))
    )
    (comp (ref "R68")
      (value "Res 0603 4k7")
      (footprint "SamacSys:RESC1608X55N")
      (description "Thick Film Resistors - SMD 0603 4.7Kohms 0.2W 1% AEC-Q200")
      (fields
        (field (name "MANUFACTURER_PART_NUMBER") "ERJ-P03F4701V")
        (field (name "MOUSER PART NUMBER") "667-ERJ-P03F4701V")
      )
      (libsource (lib "SamacSys") (part "Res 0603 4k7"))
    )
    (comp (ref "R69")
      (value "Res 0603 4k7")
      (footprint "SamacSys:RESC1608X55N")
      (description "Thick Film Resistors - SMD 0603 4.7Kohms 0.2W 1% AEC-Q200")
      (fields
        (field (name "MANUFACTURER_PART_NUMBER") "ERJ-P03F4701V")
        (field (name "MOUSER PART NUMBER") "667-ERJ-P03F4701V")
      )
      (libsource (lib "SamacSys") (part "Res 0603 4k7"))
    )
    (comp (ref "R70")
      (value "Res 0603 4k7")
      (footprint "SamacSys:RESC1608X55N")
      (description "Thick Film Resistors - SMD 0603 4.7Kohms 0.2W 1% AEC-Q200")
      (fields
        (field (name "MANUFACTURER_PART_NUMBER") "ERJ-P03F4701V")
        (field (name "MOUSER PART NUMBER") "667-ERJ-P03F4701V")
      )
      (libsource (lib "SamacSys") (part "Res 0603 4k7"))
    )
    (comp (ref "R71")
      (value "120R")
      (footprint "SamacSys:RESC1608X55N")
      (description "Thick Film Resistors - SMD 0603 120ohms 1% AEC-Q200")
      (fields
        (field (name "MANUFACTURER_PART_NUMBER") "ERJ-3EKF1200V")
        (field (name "MOUSER PART NUMBER") "667-ERJ-3EKF1200V")
      )
      (libsource (lib "SamacSys") (part "Res 0603 120R"))
    )
    (comp (ref "R72")
      (value "120R")
      (footprint "SamacSys:RESC1608X55N")
      (description "Thick Film Resistors - SMD 0603 120ohms 1% AEC-Q200")
      (fields
        (field (name "MANUFACTURER_PART_NUMBER") "ERJ-3EKF1200V")
        (field (name "MOUSER PART NUMBER") "667-ERJ-3EKF1200V")
      )
      (libsource (lib "SamacSys") (part "Res 0603 120R"))
    )
    (comp (ref "R73")
      (value "Res 0603 4k7")
      (footprint "SamacSys:RESC1608X55N")
      (description "Thick Film Resistors - SMD 0603 4.7Kohms 0.2W 1% AEC-Q200")
      (fields
        (field (name "MANUFACTURER_PART_NUMBER") "ERJ-P03F4701V")
        (field (name "MOUSER PART NUMBER") "667-ERJ-P03F4701V")
      )
      (libsource (lib "SamacSys") (part "Res 0603 4k7"))
    )
    (comp (ref "R74")
      (value "Res 0603 4k7")
      (footprint "SamacSys:RESC1608X55N")
      (description "Thick Film Resistors - SMD 0603 4.7Kohms 0.2W 1% AEC-Q200")
      (fields
        (field (name "MANUFACTURER_PART_NUMBER") "ERJ-P03F4701V")
        (field (name "MOUSER PART NUMBER") "667-ERJ-P03F4701V")
      )
      (libsource (lib "SamacSys") (part "Res 0603 4k7"))
    )
    (comp (ref "R75")
      (value "Res 0603 4k7")
      (footprint "SamacSys:RESC1608X55N")
      (description "Thick Film Resistors - SMD 0603 4.7Kohms 0.2W 1% AEC-Q200")
      (fields
        (field (name "MANUFACTURER_PART_NUMBER") "ERJ-P03F4701V")
        (field (name "MOUSER PART NUMBER") "667-ERJ-P03F4701V")
      )
      (libsource (lib "SamacSys") (part "Res 0603 4k7"))
    )
    (comp (ref "R76")
      (value "Res 0603 4k7")
      (footprint "SamacSys:RESC1608X55N")
      (description "Thick Film Resistors - SMD 0603 4.7Kohms 0.2W 1% AEC-Q200")
      (fields
        (field (name "MANUFACTURER_PART_NUMBER") "ERJ-P03F4701V")
        (field (name "MOUSER PART NUMBER") "667-ERJ-P03F4701V")
      )
      (libsource (lib "SamacSys") (part "Res 0603 4k7"))
    )
    (comp (ref "R77")
      (value "56k")
      (footprint "SamacSys:RESC1608X55N")
      (description "Thick Film Resistors - SMD 0603 56Kohms 1% AEC-Q200")
      (fields
        (field (name "MANUFACTURER_PART_NUMBER") "ERJ-3EKF5602V")
        (field (name "MOUSER PART NUMBER") "667-ERJ-3EKF5602V")
      )
      (libsource (lib "SamacSys") (part "Res 0603 56k"))
    )
    (comp (ref "R78")
      (value "56k")
      (footprint "SamacSys:RESC1608X55N")
      (description "Thick Film Resistors - SMD 0603 56Kohms 1% AEC-Q200")
      (fields
        (field (name "MANUFACTURER_PART_NUMBER") "ERJ-3EKF5602V")
        (field (name "MOUSER PART NUMBER") "667-ERJ-3EKF5602V")
      )
      (libsource (lib "SamacSys") (part "Res 0603 56k"))
    )
    (comp (ref "R79")
      (value "Res 0603 1k5")
      (footprint "SamacSys:RESC1608X55N")
      (description "Thick Film Resistors - SMD 1.5 kOhms 100mW 0603 1%")
      (fields
        (field (name "MANUFACTURER_PART_NUMBER") "RC0603FR-071K5L")
        (field (name "MOUSER PART NUMBER") "603-RC0603FR-071K5L")
      )
      (libsource (lib "SamacSys") (part "Res 0603 1k5"))
    )
    (comp (ref "R80")
      (value "Res 0603 1k5")
      (footprint "SamacSys:RESC1608X55N")
      (description "Thick Film Resistors - SMD 1.5 kOhms 100mW 0603 1%")
      (fields
        (field (name "MANUFACTURER_PART_NUMBER") "RC0603FR-071K5L")
        (field (name "MOUSER PART NUMBER") "603-RC0603FR-071K5L")
      )
      (libsource (lib "SamacSys") (part "Res 0603 1k5"))
    )
    (comp (ref "R81")
      (value "Res 0603 1k5")
      (footprint "SamacSys:RESC1608X55N")
      (description "Thick Film Resistors - SMD 1.5 kOhms 100mW 0603 1%")
      (fields
        (field (name "MANUFACTURER_PART_NUMBER") "RC0603FR-071K5L")
        (field (name "MOUSER PART NUMBER") "603-RC0603FR-071K5L")
      )
      (libsource (lib "") (part "Res 0603 1k5_1"))
    )
    (comp (ref "R82")
      (value "Res 0603 4k7")
      (footprint "SamacSys:RESC1608X55N")
      (description "Thick Film Resistors - SMD 0603 4.7Kohms 0.2W 1% AEC-Q200")
      (fields
        (field (name "MANUFACTURER_PART_NUMBER") "ERJ-P03F4701V")
        (field (name "MOUSER PART NUMBER") "667-ERJ-P03F4701V")
      )
      (libsource (lib "SamacSys") (part "Res 0603 4k7"))
    )
    (comp (ref "R83")
      (value "Res 0603 4k7")
      (footprint "SamacSys:RESC1608X55N")
      (description "Thick Film Resistors - SMD 0603 4.7Kohms 0.2W 1% AEC-Q200")
      (fields
        (field (name "MANUFACTURER_PART_NUMBER") "ERJ-P03F4701V")
        (field (name "MOUSER PART NUMBER") "667-ERJ-P03F4701V")
      )
      (libsource (lib "SamacSys") (part "Res 0603 4k7"))
    )
    (comp (ref "R84")
      (value "120R")
      (footprint "SamacSys:RESC1608X55N")
      (description "Thick Film Resistors - SMD 0603 120ohms 1% AEC-Q200")
      (fields
        (field (name "MANUFACTURER_PART_NUMBER") "ERJ-3EKF1200V")
        (field (name "MOUSER PART NUMBER") "667-ERJ-3EKF1200V")
      )
      (libsource (lib "SamacSys") (part "Res 0603 120R"))
    )
    (comp (ref "R85")
      (value "Res 0603 4k7")
      (footprint "SamacSys:RESC1608X55N")
      (description "Thick Film Resistors - SMD 0603 4.7Kohms 0.2W 1% AEC-Q200")
      (fields
        (field (name "MANUFACTURER_PART_NUMBER") "ERJ-P03F4701V")
        (field (name "MOUSER PART NUMBER") "667-ERJ-P03F4701V")
      )
      (libsource (lib "SamacSys") (part "Res 0603 4k7"))
    )
    (comp (ref "R86")
      (value "Res 0603 4k7")
      (footprint "SamacSys:RESC1608X55N")
      (description "Thick Film Resistors - SMD 0603 4.7Kohms 0.2W 1% AEC-Q200")
      (fields
        (field (name "MANUFACTURER_PART_NUMBER") "ERJ-P03F4701V")
        (field (name "MOUSER PART NUMBER") "667-ERJ-P03F4701V")
      )
      (libsource (lib "SamacSys") (part "Res 0603 4k7"))
    )
    (comp (ref "R87")
      (value "56k")
      (footprint "SamacSys:RESC1608X55N")
      (description "Thick Film Resistors - SMD 0603 56Kohms 1% AEC-Q200")
      (fields
        (field (name "MANUFACTURER_PART_NUMBER") "ERJ-3EKF5602V")
        (field (name "MOUSER PART NUMBER") "667-ERJ-3EKF5602V")
      )
      (libsource (lib "SamacSys") (part "Res 0603 56k"))
    )
    (comp (ref "R88")
      (value "Res 0603 1k5")
      (footprint "SamacSys:RESC1608X55N")
      (description "Thick Film Resistors - SMD 1.5 kOhms 100mW 0603 1%")
      (fields
        (field (name "MANUFACTURER_PART_NUMBER") "RC0603FR-071K5L")
        (field (name "MOUSER PART NUMBER") "603-RC0603FR-071K5L")
      )
      (libsource (lib "SamacSys") (part "Res 0603 1k5"))
    )
  )
  (nets
    (net (code "1") (name "/Port_1_N") (class "Default")
      (node (ref "F1") (pin "2") (pinfunction "2_2") (pintype "passive"))
      (node (ref "J4") (pin "3") (pinfunction "3_3") (pintype "passive"))
      (node (ref "R39") (pin "2") (pinfunction "2_2") (pintype "passive"))
    )
    (net (code "2") (name "/Port_1_P") (class "Default")
      (node (ref "F3") (pin "2") (pinfunction "2_2") (pintype "passive"))
      (node (ref "J4") (pin "1") (pinfunction "1_1") (pintype "passive"))
      (node (ref "R39") (pin "1") (pinfunction "1_1") (pintype "passive"))
    )
    (net (code "3") (name "/Port_2_N") (class "Default")
      (node (ref "F5") (pin "2") (pinfunction "2_2") (pintype "passive"))
      (node (ref "J6") (pin "3") (pinfunction "3_3") (pintype "passive"))
      (node (ref "R55") (pin "2") (pinfunction "2_2") (pintype "passive"))
    )
    (net (code "4") (name "/Port_2_P") (class "Default")
      (node (ref "F7") (pin "2") (pinfunction "2_2") (pintype "passive"))
      (node (ref "J6") (pin "1") (pinfunction "1_1") (pintype "passive"))
      (node (ref "R55") (pin "1") (pinfunction "1_1") (pintype "passive"))
    )
    (net (code "5") (name "/Port_3_N") (class "Default")
      (node (ref "F9") (pin "2") (pinfunction "2_2") (pintype "passive"))
      (node (ref "J8") (pin "3") (pinfunction "3_3") (pintype "passive"))
      (node (ref "R71") (pin "2") (pinfunction "2_2") (pintype "passive"))
    )
    (net (code "6") (name "/Port_3_P") (class "Default")
      (node (ref "F11") (pin "2") (pinfunction "2_2") (pintype "passive"))
      (node (ref "J8") (pin "1") (pinfunction "1_1") (pintype "passive"))
      (node (ref "R71") (pin "1") (pinfunction "1_1") (pintype "passive"))
    )
    (net (code "7") (name "/Port_4_N") (class "Default")
      (node (ref "F2") (pin "2") (pinfunction "2_2") (pintype "passive"))
      (node (ref "J5") (pin "3") (pinfunction "3_3") (pintype "passive"))
      (node (ref "R40") (pin "2") (pinfunction "2_2") (pintype "passive"))
    )
    (net (code "8") (name "/Port_4_P") (class "Default")
      (node (ref "F4") (pin "2") (pinfunction "2_2") (pintype "passive"))
      (node (ref "J5") (pin "1") (pinfunction "1_1") (pintype "passive"))
      (node (ref "R40") (pin "1") (pinfunction "1_1") (pintype "passive"))
    )
    (net (code "9") (name "/Port_5_N") (class "Default")
      (node (ref "F6") (pin "2") (pinfunction "2_2") (pintype "passive"))
      (node (ref "J7") (pin "3") (pinfunction "3_3") (pintype "passive"))
      (node (ref "R56") (pin "2") (pinfunction "2_2") (pintype "passive"))
    )
    (net (code "10") (name "/Port_5_P") (class "Default")
      (node (ref "F8") (pin "2") (pinfunction "2_2") (pintype "passive"))
      (node (ref "J7") (pin "1") (pinfunction "1_1") (pintype "passive"))
      (node (ref "R56") (pin "1") (pinfunction "1_1") (pintype "passive"))
    )
    (net (code "11") (name "/Port_6_N") (class "Default")
      (node (ref "F10") (pin "2") (pinfunction "2_2") (pintype "passive"))
      (node (ref "J9") (pin "3") (pinfunction "3_3") (pintype "passive"))
      (node (ref "R72") (pin "2") (pinfunction "2_2") (pintype "passive"))
    )
    (net (code "12") (name "/Port_6_P") (class "Default")
      (node (ref "F12") (pin "2") (pinfunction "2_2") (pintype "passive"))
      (node (ref "J9") (pin "1") (pinfunction "1_1") (pintype "passive"))
      (node (ref "R72") (pin "1") (pinfunction "1_1") (pintype "passive"))
    )
    (net (code "13") (name "/Port_out_N") (class "Default")
      (node (ref "F13") (pin "2") (pinfunction "2_2") (pintype "passive"))
      (node (ref "J10") (pin "1") (pinfunction "1_1") (pintype "passive"))
      (node (ref "R84") (pin "2") (pinfunction "2_2") (pintype "passive"))
    )
    (net (code "14") (name "/Port_out_P") (class "Default")
      (node (ref "F14") (pin "2") (pinfunction "2_2") (pintype "passive"))
      (node (ref "J10") (pin "3") (pinfunction "3_3") (pintype "passive"))
      (node (ref "R84") (pin "1") (pinfunction "1_1") (pintype "passive"))
    )
    (net (code "15") (name "/RS485_RX1") (class "Default")
      (node (ref "IC4") (pin "4") (pinfunction "H=~{B}_4") (pintype "passive"))
      (node (ref "IC4") (pin "5") (pinfunction "C_5") (pintype "passive"))
    )
    (net (code "16") (name "/RS485_RX2") (class "Default")
      (node (ref "IC8") (pin "4") (pinfunction "H=~{B}_4") (pintype "passive"))
      (node (ref "IC8") (pin "5") (pinfunction "C_5") (pintype "passive"))
    )
    (net (code "17") (name "/RS485_RX3") (class "Default")
      (node (ref "IC12") (pin "4") (pinfunction "H=~{B}_4") (pintype "passive"))
      (node (ref "IC12") (pin "5") (pinfunction "C_5") (pintype "passive"))
    )
    (net (code "18") (name "/RS485_RX4") (class "Default")
      (node (ref "IC5") (pin "4") (pinfunction "H=~{B}_4") (pintype "passive"))
      (node (ref "IC5") (pin "5") (pinfunction "C_5") (pintype "passive"))
    )
    (net (code "19") (name "/RS485_RX5") (class "Default")
      (node (ref "IC9") (pin "4") (pinfunction "H=~{B}_4") (pintype "passive"))
      (node (ref "IC9") (pin "5") (pinfunction "C_5") (pintype "passive"))
    )
    (net (code "20") (name "/RS485_RX6") (class "Default")
      (node (ref "IC13") (pin "4") (pinfunction "H=~{B}_4") (pintype "passive"))
      (node (ref "IC13") (pin "5") (pinfunction "C_5") (pintype "passive"))
    )
    (net (code "21") (name "/RS485_TX1") (class "Default")
      (node (ref "IC4") (pin "1") (pinfunction "A_1") (pintype "passive"))
      (node (ref "R43") (pin "1") (pinfunction "1_1") (pintype "passive"))
    )
    (net (code "22") (name "/RS485_TX2") (class "Default")
      (node (ref "IC8") (pin "1") (pinfunction "A_1") (pintype "passive"))
      (node (ref "R59") (pin "1") (pinfunction "1_1") (pintype "passive"))
    )
    (net (code "23") (name "/RS485_TX3") (class "Default")
      (node (ref "IC12") (pin "1") (pinfunction "A_1") (pintype "passive"))
      (node (ref "R75") (pin "1") (pinfunction "1_1") (pintype "passive"))
    )
    (net (code "24") (name "/RS485_TX4") (class "Default")
      (node (ref "IC5") (pin "1") (pinfunction "A_1") (pintype "passive"))
      (node (ref "R44") (pin "1") (pinfunction "1_1") (pintype "passive"))
    )
    (net (code "25") (name "/RS485_TX5") (class "Default")
      (node (ref "IC9") (pin "1") (pinfunction "A_1") (pintype "passive"))
      (node (ref "R60") (pin "1") (pinfunction "1_1") (pintype "passive"))
    )
    (net (code "26") (name "/RS485_TX6") (class "Default")
      (node (ref "IC13") (pin "1") (pinfunction "A_1") (pintype "passive"))
      (node (ref "R76") (pin "1") (pinfunction "1_1") (pintype "passive"))
    )
    (net (code "27") (name "/SLAVE_RS485_RX") (class "Default")
      (node (ref "IC16") (pin "4") (pinfunction "H=~{B}_4") (pintype "passive"))
      (node (ref "IC16") (pin "5") (pinfunction "C_5") (pintype "passive"))
    )
    (net (code "28") (name "/SLAVE_RS485_TX") (class "Default")
      (node (ref "IC16") (pin "1") (pinfunction "A_1") (pintype "passive"))
      (node (ref "R86") (pin "1") (pinfunction "1_1") (pintype "passive"))
    )
    (net (code "29") (name "3V3") (class "Default")
      (node (ref "C36") (pin "1") (pinfunction "1_1") (pintype "passive"))
      (node (ref "C37") (pin "1") (pinfunction "1_1") (pintype "passive"))
      (node (ref "C40") (pin "1") (pinfunction "1_1") (pintype "passive"))
      (node (ref "C41") (pin "1") (pinfunction "1_1") (pintype "passive"))
      (node (ref "C44") (pin "1") (pinfunction "1_1") (pintype "passive"))
      (node (ref "C45") (pin "1") (pinfunction "1_1") (pintype "passive"))
      (node (ref "C48") (pin "1") (pinfunction "1_1") (pintype "passive"))
      (node (ref "IC10") (pin "8") (pinfunction "VCC_8") (pintype "passive"))
      (node (ref "IC11") (pin "8") (pinfunction "VCC_8") (pintype "passive"))
      (node (ref "IC12") (pin "14") (pinfunction "VDD_14") (pintype "passive"))
      (node (ref "IC13") (pin "14") (pinfunction "VDD_14") (pintype "passive"))
      (node (ref "IC14") (pin "8") (pinfunction "VCC_8") (pintype "passive"))
      (node (ref "IC15") (pin "8") (pinfunction "VCC_8") (pintype "passive"))
      (node (ref "IC16") (pin "14") (pinfunction "VDD_14") (pintype "passive"))
      (node (ref "IC17") (pin "8") (pinfunction "VCC_8") (pintype "passive"))
      (node (ref "IC4") (pin "14") (pinfunction "VDD_14") (pintype "passive"))
      (node (ref "IC5") (pin "14") (pinfunction "VDD_14") (pintype "passive"))
      (node (ref "IC6") (pin "8") (pinfunction "VCC_8") (pintype "passive"))
      (node (ref "IC7") (pin "8") (pinfunction "VCC_8") (pintype "passive"))
      (node (ref "IC8") (pin "14") (pinfunction "VDD_14") (pintype "passive"))
      (node (ref "IC9") (pin "14") (pinfunction "VDD_14") (pintype "passive"))
      (node (ref "R35") (pin "2") (pinfunction "2_2") (pintype "passive"))
      (node (ref "R36") (pin "2") (pinfunction "2_2") (pintype "passive"))
      (node (ref "R41") (pin "1") (pinfunction "1_1") (pintype "passive"))
      (node (ref "R42") (pin "1") (pinfunction "1_1") (pintype "passive"))
      (node (ref "R43") (pin "2") (pinfunction "2_2") (pintype "passive"))
      (node (ref "R44") (pin "2") (pinfunction "2_2") (pintype "passive"))
      (node (ref "R51") (pin "2") (pinfunction "2_2") (pintype "passive"))
      (node (ref "R52") (pin "2") (pinfunction "2_2") (pintype "passive"))
      (node (ref "R57") (pin "1") (pinfunction "1_1") (pintype "passive"))
      (node (ref "R58") (pin "1") (pinfunction "1_1") (pintype "passive"))
      (node (ref "R59") (pin "2") (pinfunction "2_2") (pintype "passive"))
      (node (ref "R60") (pin "2") (pinfunction "2_2") (pintype "passive"))
      (node (ref "R67") (pin "2") (pinfunction "2_2") (pintype "passive"))
      (node (ref "R68") (pin "2") (pinfunction "2_2") (pintype "passive"))
      (node (ref "R73") (pin "1") (pinfunction "1_1") (pintype "passive"))
      (node (ref "R74") (pin "1") (pinfunction "1_1") (pintype "passive"))
      (node (ref "R75") (pin "2") (pinfunction "2_2") (pintype "passive"))
      (node (ref "R76") (pin "2") (pinfunction "2_2") (pintype "passive"))
      (node (ref "R82") (pin "2") (pinfunction "2_2") (pintype "passive"))
      (node (ref "R85") (pin "1") (pinfunction "1_1") (pintype "passive"))
      (node (ref "R86") (pin "2") (pinfunction "2_2") (pintype "passive"))
    )
    (net (code "30") (name "GND") (class "Default")
      (node (ref "C36") (pin "2") (pinfunction "2_2") (pintype "passive"))
      (node (ref "C37") (pin "2") (pinfunction "2_2") (pintype "passive"))
      (node (ref "C38") (pin "1") (pinfunction "1_1") (pintype "passive"))
      (node (ref "C39") (pin "1") (pinfunction "1_1") (pintype "passive"))
      (node (ref "C40") (pin "2") (pinfunction "2_2") (pintype "passive"))
      (node (ref "C41") (pin "2") (pinfunction "2_2") (pintype "passive"))
      (node (ref "C42") (pin "1") (pinfunction "1_1") (pintype "passive"))
      (node (ref "C43") (pin "1") (pinfunction "1_1") (pintype "passive"))
      (node (ref "C44") (pin "2") (pinfunction "2_2") (pintype "passive"))
      (node (ref "C45") (pin "2") (pinfunction "2_2") (pintype "passive"))
      (node (ref "C46") (pin "1") (pinfunction "1_1") (pintype "passive"))
      (node (ref "C47") (pin "1") (pinfunction "1_1") (pintype "passive"))
      (node (ref "C48") (pin "2") (pinfunction "2_2") (pintype "passive"))
      (node (ref "C49") (pin "1") (pinfunction "1_1") (pintype "passive"))
      (node (ref "D10") (pin "1") (pinfunction "1_1") (pintype "passive"))
      (node (ref "D11") (pin "2") (pinfunction "2_2") (pintype "passive"))
      (node (ref "D12") (pin "2") (pinfunction "2_2") (pintype "passive"))
      (node (ref "D17") (pin "1") (pinfunction "1_1") (pintype "passive"))
      (node (ref "D18") (pin "1") (pinfunction "1_1") (pintype "passive"))
      (node (ref "D19") (pin "2") (pinfunction "2_2") (pintype "passive"))
      (node (ref "D20") (pin "2") (pinfunction "2_2") (pintype "passive"))
      (node (ref "D25") (pin "1") (pinfunction "1_1") (pintype "passive"))
      (node (ref "D26") (pin "1") (pinfunction "1_1") (pintype "passive"))
      (node (ref "D27") (pin "2") (pinfunction "2_2") (pintype "passive"))
      (node (ref "D3") (pin "2") (pinfunction "2_2") (pintype "passive"))
      (node (ref "D30") (pin "1") (pinfunction "1_1") (pintype "passive"))
      (node (ref "D4") (pin "2") (pinfunction "2_2") (pintype "passive"))
      (node (ref "D9") (pin "1") (pinfunction "1_1") (pintype "passive"))
      (node (ref "IC10") (pin "5") (pinfunction "GND_5") (pintype "passive"))
      (node (ref "IC11") (pin "5") (pinfunction "GND_5") (pintype "passive"))
      (node (ref "IC12") (pin "7") (pinfunction "VSS_7") (pintype "passive"))
      (node (ref "IC13") (pin "7") (pinfunction "VSS_7") (pintype "passive"))
      (node (ref "IC14") (pin "5") (pinfunction "GND_5") (pintype "passive"))
      (node (ref "IC15") (pin "5") (pinfunction "GND_5") (pintype "passive"))
      (node (ref "IC16") (pin "7") (pinfunction "VSS_7") (pintype "passive"))
      (node (ref "IC17") (pin "5") (pinfunction "GND_5") (pintype "passive"))
      (node (ref "IC4") (pin "7") (pinfunction "VSS_7") (pintype "passive"))
      (node (ref "IC5") (pin "7") (pinfunction "VSS_7") (pintype "passive"))
      (node (ref "IC6") (pin "5") (pinfunction "GND_5") (pintype "passive"))
      (node (ref "IC7") (pin "5") (pinfunction "GND_5") (pintype "passive"))
      (node (ref "IC8") (pin "7") (pinfunction "VSS_7") (pintype "passive"))
      (node (ref "IC9") (pin "7") (pinfunction "VSS_7") (pintype "passive"))
      (node (ref "J10") (pin "2") (pinfunction "2_2") (pintype "passive"))
      (node (ref "J10") (pin "4") (pinfunction "4_4") (pintype "passive"))
      (node (ref "J4") (pin "2") (pinfunction "2_2") (pintype "passive"))
      (node (ref "J4") (pin "4") (pinfunction "4_4") (pintype "passive"))
      (node (ref "J5") (pin "2") (pinfunction "2_2") (pintype "passive"))
      (node (ref "J5") (pin "4") (pinfunction "4_4") (pintype "passive"))
      (node (ref "J6") (pin "2") (pinfunction "2_2") (pintype "passive"))
      (node (ref "J6") (pin "4") (pinfunction "4_4") (pintype "passive"))
      (node (ref "J7") (pin "2") (pinfunction "2_2") (pintype "passive"))
      (node (ref "J7") (pin "4") (pinfunction "4_4") (pintype "passive"))
      (node (ref "J8") (pin "2") (pinfunction "2_2") (pintype "passive"))
      (node (ref "J8") (pin "4") (pinfunction "4_4") (pintype "passive"))
      (node (ref "J9") (pin "2") (pinfunction "2_2") (pintype "passive"))
      (node (ref "J9") (pin "4") (pinfunction "4_4") (pintype "passive"))
      (node (ref "LED13") (pin "1") (pinfunction "K_1") (pintype "passive"))
      (node (ref "LED14") (pin "1") (pinfunction "K_1") (pintype "passive"))
      (node (ref "LED15") (pin "1") (pinfunction "K_1") (pintype "passive"))
      (node (ref "LED16") (pin "1") (pinfunction "K_1") (pintype "passive"))
      (node (ref "LED17") (pin "1") (pinfunction "K_1") (pintype "passive"))
      (node (ref "LED18") (pin "1") (pinfunction "K_1") (pintype "passive"))
      (node (ref "LED19") (pin "1") (pinfunction "K_1") (pintype "passive"))
      (node (ref "LED20") (pin "1") (pinfunction "K_1") (pintype "passive"))
      (node (ref "LED21") (pin "1") (pinfunction "K_1") (pintype "passive"))
      (node (ref "LED22") (pin "1") (pinfunction "K_1") (pintype "passive"))
      (node (ref "LED23") (pin "1") (pinfunction "K_1") (pintype "passive"))
      (node (ref "LED24") (pin "1") (pinfunction "K_1") (pintype "passive"))
      (node (ref "LED25") (pin "1") (pinfunction "K_1") (pintype "passive"))
      (node (ref "LED26") (pin "1") (pinfunction "K_1") (pintype "passive"))
      (node (ref "R37") (pin "2") (pinfunction "2_2") (pintype "passive"))
      (node (ref "R38") (pin "2") (pinfunction "2_2") (pintype "passive"))
      (node (ref "R53") (pin "2") (pinfunction "2_2") (pintype "passive"))
      (node (ref "R54") (pin "2") (pinfunction "2_2") (pintype "passive"))
      (node (ref "R69") (pin "2") (pinfunction "2_2") (pintype "passive"))
      (node (ref "R70") (pin "2") (pinfunction "2_2") (pintype "passive"))
      (node (ref "R83") (pin "2") (pinfunction "2_2") (pintype "passive"))
    )
    (net (code "31") (name "Net-(D5-A)") (class "Default")
      (node (ref "C38") (pin "2") (pinfunction "2_2") (pintype "passive"))
      (node (ref "D5") (pin "2") (pinfunction "A_2") (pintype "passive"))
      (node (ref "IC4") (pin "13") (pinfunction "F_13") (pintype "passive"))
      (node (ref "R45") (pin "1") (pinfunction "1_1") (pintype "passive"))
    )
    (net (code "32") (name "Net-(D5-K)") (class "Default")
      (node (ref "D5") (pin "1") (pinfunction "K_1") (pintype "passive"))
      (node (ref "IC4") (pin "10") (pinfunction "K=~{E}_10") (pintype "passive"))
      (node (ref "IC6") (pin "4") (pinfunction "DI_4") (pintype "passive"))
      (node (ref "R45") (pin "2") (pinfunction "2_2") (pintype "passive"))
    )
    (net (code "33") (name "Net-(D7-A)") (class "Default")
      (node (ref "C39") (pin "2") (pinfunction "2_2") (pintype "passive"))
      (node (ref "D7") (pin "2") (pinfunction "A_2") (pintype "passive"))
      (node (ref "IC5") (pin "13") (pinfunction "F_13") (pintype "passive"))
      (node (ref "R46") (pin "1") (pinfunction "1_1") (pintype "passive"))
    )
    (net (code "34") (name "Net-(D7-K)") (class "Default")
      (node (ref "D7") (pin "1") (pinfunction "K_1") (pintype "passive"))
      (node (ref "IC5") (pin "10") (pinfunction "K=~{E}_10") (pintype "passive"))
      (node (ref "IC7") (pin "4") (pinfunction "DI_4") (pintype "passive"))
      (node (ref "R46") (pin "2") (pinfunction "2_2") (pintype "passive"))
    )
    (net (code "35") (name "Net-(D13-A)") (class "Default")
      (node (ref "C42") (pin "2") (pinfunction "2_2") (pintype "passive"))
      (node (ref "D13") (pin "2") (pinfunction "A_2") (pintype "passive"))
      (node (ref "IC8") (pin "13") (pinfunction "F_13") (pintype "passive"))
      (node (ref "R61") (pin "1") (pinfunction "1_1") (pintype "passive"))
    )
    (net (code "36") (name "Net-(D13-K)") (class "Default")
      (node (ref "D13") (pin "1") (pinfunction "K_1") (pintype "passive"))
      (node (ref "IC10") (pin "4") (pinfunction "DI_4") (pintype "passive"))
      (node (ref "IC8") (pin "10") (pinfunction "K=~{E}_10") (pintype "passive"))
      (node (ref "R61") (pin "2") (pinfunction "2_2") (pintype "passive"))
    )
    (net (code "37") (name "Net-(D15-A)") (class "Default")
      (node (ref "C43") (pin "2") (pinfunction "2_2") (pintype "passive"))
      (node (ref "D15") (pin "2") (pinfunction "A_2") (pintype "passive"))
      (node (ref "IC9") (pin "13") (pinfunction "F_13") (pintype "passive"))
      (node (ref "R62") (pin "1") (pinfunction "1_1") (pintype "passive"))
    )
    (net (code "38") (name "Net-(D15-K)") (class "Default")
      (node (ref "D15") (pin "1") (pinfunction "K_1") (pintype "passive"))
      (node (ref "IC11") (pin "4") (pinfunction "DI_4") (pintype "passive"))
      (node (ref "IC9") (pin "10") (pinfunction "K=~{E}_10") (pintype "passive"))
      (node (ref "R62") (pin "2") (pinfunction "2_2") (pintype "passive"))
    )
    (net (code "39") (name "Net-(D21-A)") (class "Default")
      (node (ref "C46") (pin "2") (pinfunction "2_2") (pintype "passive"))
      (node (ref "D21") (pin "2") (pinfunction "A_2") (pintype "passive"))
      (node (ref "IC12") (pin "13") (pinfunction "F_13") (pintype "passive"))
      (node (ref "R77") (pin "1") (pinfunction "1_1") (pintype "passive"))
    )
    (net (code "40") (name "Net-(D21-K)") (class "Default")
      (node (ref "D21") (pin "1") (pinfunction "K_1") (pintype "passive"))
      (node (ref "IC12") (pin "10") (pinfunction "K=~{E}_10") (pintype "passive"))
      (node (ref "IC14") (pin "4") (pinfunction "DI_4") (pintype "passive"))
      (node (ref "R77") (pin "2") (pinfunction "2_2") (pintype "passive"))
    )
    (net (code "41") (name "Net-(D23-A)") (class "Default")
      (node (ref "C47") (pin "2") (pinfunction "2_2") (pintype "passive"))
      (node (ref "D23") (pin "2") (pinfunction "A_2") (pintype "passive"))
      (node (ref "IC13") (pin "13") (pinfunction "F_13") (pintype "passive"))
      (node (ref "R78") (pin "1") (pinfunction "1_1") (pintype "passive"))
    )
    (net (code "42") (name "Net-(D23-K)") (class "Default")
      (node (ref "D23") (pin "1") (pinfunction "K_1") (pintype "passive"))
      (node (ref "IC13") (pin "10") (pinfunction "K=~{E}_10") (pintype "passive"))
      (node (ref "IC15") (pin "4") (pinfunction "DI_4") (pintype "passive"))
      (node (ref "R78") (pin "2") (pinfunction "2_2") (pintype "passive"))
    )
    (net (code "43") (name "Net-(D28-A)") (class "Default")
      (node (ref "C49") (pin "2") (pinfunction "2_2") (pintype "passive"))
      (node (ref "D28") (pin "2") (pinfunction "A_2") (pintype "passive"))
      (node (ref "IC16") (pin "13") (pinfunction "F_13") (pintype "passive"))
      (node (ref "R87") (pin "1") (pinfunction "1_1") (pintype "passive"))
    )
    (net (code "44") (name "Net-(D28-K)") (class "Default")
      (node (ref "D28") (pin "1") (pinfunction "K_1") (pintype "passive"))
      (node (ref "IC16") (pin "10") (pinfunction "K=~{E}_10") (pintype "passive"))
      (node (ref "IC17") (pin "4") (pinfunction "DI_4") (pintype "passive"))
      (node (ref "R87") (pin "2") (pinfunction "2_2") (pintype "passive"))
    )
    (net (code "45") (name "Net-(IC4A-G=~{A})") (class "Default")
      (node (ref "IC4") (pin "11") (pinfunction "E_11") (pintype "passive"))
      (node (ref "IC4") (pin "2") (pinfunction "G=~{A}_2") (pintype "passive"))
      (node (ref "R47") (pin "2") (pinfunction "2_2") (pintype "passive"))
    )
    (net (code "46") (name "Net-(IC4B-B)") (class "Default")
      (node (ref "IC4") (pin "3") (pinfunction "B_3") (pintype "passive"))
      (node (ref "IC4") (pin "8") (pinfunction "J=~{D}_8") (pintype "passive"))
    )
    (net (code "47") (name "Net-(IC4C-I=~{C})") (class "Default")
      (node (ref "IC4") (pin "6") (pinfunction "I=~{C}_6") (pintype "passive"))
      (node (ref "R33") (pin "1") (pinfunction "1_1") (pintype "passive"))
    )
    (net (code "48") (name "Net-(IC4D-D)") (class "Default")
      (node (ref "IC4") (pin "9") (pinfunction "D_9") (pintype "passive"))
      (node (ref "IC6") (pin "1") (pinfunction "RO_1") (pintype "passive"))
      (node (ref "R35") (pin "1") (pinfunction "1_1") (pintype "passive"))
    )
    (net (code "49") (name "Net-(IC4F-L=~{F})") (class "Default")
      (node (ref "IC4") (pin "12") (pinfunction "L=~{F}_12") (pintype "passive"))
      (node (ref "IC6") (pin "2") (pinfunction "~{RE}_2") (pintype "passive"))
      (node (ref "IC6") (pin "3") (pinfunction "DE_3") (pintype "passive"))
    )
    (net (code "50") (name "Net-(IC5A-G=~{A})") (class "Default")
      (node (ref "IC5") (pin "11") (pinfunction "E_11") (pintype "passive"))
      (node (ref "IC5") (pin "2") (pinfunction "G=~{A}_2") (pintype "passive"))
      (node (ref "R48") (pin "2") (pinfunction "2_2") (pintype "passive"))
    )
    (net (code "51") (name "Net-(IC5B-B)") (class "Default")
      (node (ref "IC5") (pin "3") (pinfunction "B_3") (pintype "passive"))
      (node (ref "IC5") (pin "8") (pinfunction "J=~{D}_8") (pintype "passive"))
    )
    (net (code "52") (name "Net-(IC5C-I=~{C})") (class "Default")
      (node (ref "IC5") (pin "6") (pinfunction "I=~{C}_6") (pintype "passive"))
      (node (ref "R34") (pin "1") (pinfunction "1_1") (pintype "passive"))
    )
    (net (code "53") (name "Net-(IC5D-D)") (class "Default")
      (node (ref "IC5") (pin "9") (pinfunction "D_9") (pintype "passive"))
      (node (ref "IC7") (pin "1") (pinfunction "RO_1") (pintype "passive"))
      (node (ref "R36") (pin "1") (pinfunction "1_1") (pintype "passive"))
    )
    (net (code "54") (name "Net-(IC5F-L=~{F})") (class "Default")
      (node (ref "IC5") (pin "12") (pinfunction "L=~{F}_12") (pintype "passive"))
      (node (ref "IC7") (pin "2") (pinfunction "~{RE}_2") (pintype "passive"))
      (node (ref "IC7") (pin "3") (pinfunction "DE_3") (pintype "passive"))
    )
    (net (code "55") (name "Net-(IC6-A)") (class "Default")
      (node (ref "D6") (pin "1") (pinfunction "1_1") (pintype "passive"))
      (node (ref "D9") (pin "2") (pinfunction "2_2") (pintype "passive"))
      (node (ref "F3") (pin "1") (pinfunction "1_1") (pintype "passive"))
      (node (ref "IC6") (pin "6") (pinfunction "A_6") (pintype "passive"))
      (node (ref "R41") (pin "2") (pinfunction "2_2") (pintype "passive"))
    )
    (net (code "56") (name "Net-(IC6-B)") (class "Default")
      (node (ref "D3") (pin "1") (pinfunction "1_1") (pintype "passive"))
      (node (ref "D6") (pin "2") (pinfunction "2_2") (pintype "passive"))
      (node (ref "F1") (pin "1") (pinfunction "1_1") (pintype "passive"))
      (node (ref "IC6") (pin "7") (pinfunction "B_7") (pintype "passive"))
      (node (ref "R37") (pin "1") (pinfunction "1_1") (pintype "passive"))
    )
    (net (code "57") (name "Net-(IC7-A)") (class "Default")
      (node (ref "D10") (pin "2") (pinfunction "2_2") (pintype "passive"))
      (node (ref "D8") (pin "1") (pinfunction "1_1") (pintype "passive"))
      (node (ref "F4") (pin "1") (pinfunction "1_1") (pintype "passive"))
      (node (ref "IC7") (pin "6") (pinfunction "A_6") (pintype "passive"))
      (node (ref "R42") (pin "2") (pinfunction "2_2") (pintype "passive"))
    )
    (net (code "58") (name "Net-(IC7-B)") (class "Default")
      (node (ref "D4") (pin "1") (pinfunction "1_1") (pintype "passive"))
      (node (ref "D8") (pin "2") (pinfunction "2_2") (pintype "passive"))
      (node (ref "F2") (pin "1") (pinfunction "1_1") (pintype "passive"))
      (node (ref "IC7") (pin "7") (pinfunction "B_7") (pintype "passive"))
      (node (ref "R38") (pin "1") (pinfunction "1_1") (pintype "passive"))
    )
    (net (code "59") (name "Net-(IC8A-G=~{A})") (class "Default")
      (node (ref "IC8") (pin "11") (pinfunction "E_11") (pintype "passive"))
      (node (ref "IC8") (pin "2") (pinfunction "G=~{A}_2") (pintype "passive"))
      (node (ref "R63") (pin "2") (pinfunction "2_2") (pintype "passive"))
    )
    (net (code "60") (name "Net-(IC8B-B)") (class "Default")
      (node (ref "IC8") (pin "3") (pinfunction "B_3") (pintype "passive"))
      (node (ref "IC8") (pin "8") (pinfunction "J=~{D}_8") (pintype "passive"))
    )
    (net (code "61") (name "Net-(IC8C-I=~{C})") (class "Default")
      (node (ref "IC8") (pin "6") (pinfunction "I=~{C}_6") (pintype "passive"))
      (node (ref "R49") (pin "1") (pinfunction "1_1") (pintype "passive"))
    )
    (net (code "62") (name "Net-(IC9A-G=~{A})") (class "Default")
      (node (ref "IC9") (pin "11") (pinfunction "E_11") (pintype "passive"))
      (node (ref "IC9") (pin "2") (pinfunction "G=~{A}_2") (pintype "passive"))
      (node (ref "R64") (pin "2") (pinfunction "2_2") (pintype "passive"))
    )
    (net (code "63") (name "Net-(IC9B-B)") (class "Default")
      (node (ref "IC9") (pin "3") (pinfunction "B_3") (pintype "passive"))
      (node (ref "IC9") (pin "8") (pinfunction "J=~{D}_8") (pintype "passive"))
    )
    (net (code "64") (name "Net-(IC9C-I=~{C})") (class "Default")
      (node (ref "IC9") (pin "6") (pinfunction "I=~{C}_6") (pintype "passive"))
      (node (ref "R50") (pin "1") (pinfunction "1_1") (pintype "passive"))
    )
    (net (code "65") (name "Net-(IC10-A)") (class "Default")
      (node (ref "D14") (pin "1") (pinfunction "1_1") (pintype "passive"))
      (node (ref "D17") (pin "2") (pinfunction "2_2") (pintype "passive"))
      (node (ref "F7") (pin "1") (pinfunction "1_1") (pintype "passive"))
      (node (ref "IC10") (pin "6") (pinfunction "A_6") (pintype "passive"))
      (node (ref "R57") (pin "2") (pinfunction "2_2") (pintype "passive"))
    )
    (net (code "66") (name "Net-(IC10-B)") (class "Default")
      (node (ref "D11") (pin "1") (pinfunction "1_1") (pintype "passive"))
      (node (ref "D14") (pin "2") (pinfunction "2_2") (pintype "passive"))
      (node (ref "F5") (pin "1") (pinfunction "1_1") (pintype "passive"))
      (node (ref "IC10") (pin "7") (pinfunction "B_7") (pintype "passive"))
      (node (ref "R53") (pin "1") (pinfunction "1_1") (pintype "passive"))
    )
    (net (code "67") (name "Net-(IC10-DE)") (class "Default")
      (node (ref "IC10") (pin "2") (pinfunction "~{RE}_2") (pintype "passive"))
      (node (ref "IC10") (pin "3") (pinfunction "DE_3") (pintype "passive"))
      (node (ref "IC8") (pin "12") (pinfunction "L=~{F}_12") (pintype "passive"))
    )
    (net (code "68") (name "Net-(IC10-RO)") (class "Default")
      (node (ref "IC10") (pin "1") (pinfunction "RO_1") (pintype "passive"))
      (node (ref "IC8") (pin "9") (pinfunction "D_9") (pintype "passive"))
      (node (ref "R51") (pin "1") (pinfunction "1_1") (pintype "passive"))
    )
    (net (code "69") (name "Net-(IC11-A)") (class "Default")
      (node (ref "D16") (pin "1") (pinfunction "1_1") (pintype "passive"))
      (node (ref "D18") (pin "2") (pinfunction "2_2") (pintype "passive"))
      (node (ref "F8") (pin "1") (pinfunction "1_1") (pintype "passive"))
      (node (ref "IC11") (pin "6") (pinfunction "A_6") (pintype "passive"))
      (node (ref "R58") (pin "2") (pinfunction "2_2") (pintype "passive"))
    )
    (net (code "70") (name "Net-(IC11-B)") (class "Default")
      (node (ref "D12") (pin "1") (pinfunction "1_1") (pintype "passive"))
      (node (ref "D16") (pin "2") (pinfunction "2_2") (pintype "passive"))
      (node (ref "F6") (pin "1") (pinfunction "1_1") (pintype "passive"))
      (node (ref "IC11") (pin "7") (pinfunction "B_7") (pintype "passive"))
      (node (ref "R54") (pin "1") (pinfunction "1_1") (pintype "passive"))
    )
    (net (code "71") (name "Net-(IC11-DE)") (class "Default")
      (node (ref "IC11") (pin "2") (pinfunction "~{RE}_2") (pintype "passive"))
      (node (ref "IC11") (pin "3") (pinfunction "DE_3") (pintype "passive"))
      (node (ref "IC9") (pin "12") (pinfunction "L=~{F}_12") (pintype "passive"))
    )
    (net (code "72") (name "Net-(IC11-RO)") (class "Default")
      (node (ref "IC11") (pin "1") (pinfunction "RO_1") (pintype "passive"))
      (node (ref "IC9") (pin "9") (pinfunction "D_9") (pintype "passive"))
      (node (ref "R52") (pin "1") (pinfunction "1_1") (pintype "passive"))
    )
    (net (code "73") (name "Net-(IC12A-G=~{A})") (class "Default")
      (node (ref "IC12") (pin "11") (pinfunction "E_11") (pintype "passive"))
      (node (ref "IC12") (pin "2") (pinfunction "G=~{A}_2") (pintype "passive"))
      (node (ref "R79") (pin "2") (pinfunction "2_2") (pintype "passive"))
    )
    (net (code "74") (name "Net-(IC12B-B)") (class "Default")
      (node (ref "IC12") (pin "3") (pinfunction "B_3") (pintype "passive"))
      (node (ref "IC12") (pin "8") (pinfunction "J=~{D}_8") (pintype "passive"))
    )
    (net (code "75") (name "Net-(IC12C-I=~{C})") (class "Default")
      (node (ref "IC12") (pin "6") (pinfunction "I=~{C}_6") (pintype "passive"))
      (node (ref "R65") (pin "1") (pinfunction "1_1") (pintype "passive"))
    )
    (net (code "76") (name "Net-(IC12D-D)") (class "Default")
      (node (ref "IC12") (pin "9") (pinfunction "D_9") (pintype "passive"))
      (node (ref "IC14") (pin "1") (pinfunction "RO_1") (pintype "passive"))
      (node (ref "R67") (pin "1") (pinfunction "1_1") (pintype "passive"))
    )
    (net (code "77") (name "Net-(IC12F-L=~{F})") (class "Default")
      (node (ref "IC12") (pin "12") (pinfunction "L=~{F}_12") (pintype "passive"))
      (node (ref "IC14") (pin "2") (pinfunction "~{RE}_2") (pintype "passive"))
      (node (ref "IC14") (pin "3") (pinfunction "DE_3") (pintype "passive"))
    )
    (net (code "78") (name "Net-(IC13A-G=~{A})") (class "Default")
      (node (ref "IC13") (pin "11") (pinfunction "E_11") (pintype "passive"))
      (node (ref "IC13") (pin "2") (pinfunction "G=~{A}_2") (pintype "passive"))
      (node (ref "R80") (pin "2") (pinfunction "2_2") (pintype "passive"))
    )
    (net (code "79") (name "Net-(IC13B-B)") (class "Default")
      (node (ref "IC13") (pin "3") (pinfunction "B_3") (pintype "passive"))
      (node (ref "IC13") (pin "8") (pinfunction "J=~{D}_8") (pintype "passive"))
    )
    (net (code "80") (name "Net-(IC13C-I=~{C})") (class "Default")
      (node (ref "IC13") (pin "6") (pinfunction "I=~{C}_6") (pintype "passive"))
      (node (ref "R66") (pin "1") (pinfunction "1_1") (pintype "passive"))
    )
    (net (code "81") (name "Net-(IC13D-D)") (class "Default")
      (node (ref "IC13") (pin "9") (pinfunction "D_9") (pintype "passive"))
      (node (ref "IC15") (pin "1") (pinfunction "RO_1") (pintype "passive"))
      (node (ref "R68") (pin "1") (pinfunction "1_1") (pintype "passive"))
    )
    (net (code "82") (name "Net-(IC13F-L=~{F})") (class "Default")
      (node (ref "IC13") (pin "12") (pinfunction "L=~{F}_12") (pintype "passive"))
      (node (ref "IC15") (pin "2") (pinfunction "~{RE}_2") (pintype "passive"))
      (node (ref "IC15") (pin "3") (pinfunction "DE_3") (pintype "passive"))
    )
    (net (code "83") (name "Net-(IC14-A)") (class "Default")
      (node (ref "D22") (pin "1") (pinfunction "1_1") (pintype "passive"))
      (node (ref "D25") (pin "2") (pinfunction "2_2") (pintype "passive"))
      (node (ref "F11") (pin "1") (pinfunction "1_1") (pintype "passive"))
      (node (ref "IC14") (pin "6") (pinfunction "A_6") (pintype "passive"))
      (node (ref "R73") (pin "2") (pinfunction "2_2") (pintype "passive"))
    )
    (net (code "84") (name "Net-(IC14-B)") (class "Default")
      (node (ref "D19") (pin "1") (pinfunction "1_1") (pintype "passive"))
      (node (ref "D22") (pin "2") (pinfunction "2_2") (pintype "passive"))
      (node (ref "F9") (pin "1") (pinfunction "1_1") (pintype "passive"))
      (node (ref "IC14") (pin "7") (pinfunction "B_7") (pintype "passive"))
      (node (ref "R69") (pin "1") (pinfunction "1_1") (pintype "passive"))
    )
    (net (code "85") (name "Net-(IC15-A)") (class "Default")
      (node (ref "D24") (pin "1") (pinfunction "1_1") (pintype "passive"))
      (node (ref "D26") (pin "2") (pinfunction "2_2") (pintype "passive"))
      (node (ref "F12") (pin "1") (pinfunction "1_1") (pintype "passive"))
      (node (ref "IC15") (pin "6") (pinfunction "A_6") (pintype "passive"))
      (node (ref "R74") (pin "2") (pinfunction "2_2") (pintype "passive"))
    )
    (net (code "86") (name "Net-(IC15-B)") (class "Default")
      (node (ref "D20") (pin "1") (pinfunction "1_1") (pintype "passive"))
      (node (ref "D24") (pin "2") (pinfunction "2_2") (pintype "passive"))
      (node (ref "F10") (pin "1") (pinfunction "1_1") (pintype "passive"))
      (node (ref "IC15") (pin "7") (pinfunction "B_7") (pintype "passive"))
      (node (ref "R70") (pin "1") (pinfunction "1_1") (pintype "passive"))
    )
    (net (code "87") (name "Net-(IC16A-G=~{A})") (class "Default")
      (node (ref "IC16") (pin "11") (pinfunction "E_11") (pintype "passive"))
      (node (ref "IC16") (pin "2") (pinfunction "G=~{A}_2") (pintype "passive"))
      (node (ref "R88") (pin "2") (pinfunction "2_2") (pintype "passive"))
    )
    (net (code "88") (name "Net-(IC16B-B)") (class "Default")
      (node (ref "IC16") (pin "3") (pinfunction "B_3") (pintype "passive"))
      (node (ref "IC16") (pin "8") (pinfunction "J=~{D}_8") (pintype "passive"))
    )
    (net (code "89") (name "Net-(IC16C-I=~{C})") (class "Default")
      (node (ref "IC16") (pin "6") (pinfunction "I=~{C}_6") (pintype "passive"))
      (node (ref "R81") (pin "1") (pinfunction "1_1") (pintype "passive"))
    )
    (net (code "90") (name "Net-(IC16D-D)") (class "Default")
      (node (ref "IC16") (pin "9") (pinfunction "D_9") (pintype "passive"))
      (node (ref "IC17") (pin "1") (pinfunction "RO_1") (pintype "passive"))
      (node (ref "R82") (pin "1") (pinfunction "1_1") (pintype "passive"))
    )
    (net (code "91") (name "Net-(IC16F-L=~{F})") (class "Default")
      (node (ref "IC16") (pin "12") (pinfunction "L=~{F}_12") (pintype "passive"))
      (node (ref "IC17") (pin "2") (pinfunction "~{RE}_2") (pintype "passive"))
      (node (ref "IC17") (pin "3") (pinfunction "DE_3") (pintype "passive"))
    )
    (net (code "92") (name "Net-(IC17-A)") (class "Default")
      (node (ref "D29") (pin "1") (pinfunction "1_1") (pintype "passive"))
      (node (ref "D30") (pin "2") (pinfunction "2_2") (pintype "passive"))
      (node (ref "F14") (pin "1") (pinfunction "1_1") (pintype "passive"))
      (node (ref "IC17") (pin "6") (pinfunction "A_6") (pintype "passive"))
      (node (ref "R85") (pin "2") (pinfunction "2_2") (pintype "passive"))
    )
    (net (code "93") (name "Net-(IC17-B)") (class "Default")
      (node (ref "D27") (pin "1") (pinfunction "1_1") (pintype "passive"))
      (node (ref "D29") (pin "2") (pinfunction "2_2") (pintype "passive"))
      (node (ref "F13") (pin "1") (pinfunction "1_1") (pintype "passive"))
      (node (ref "IC17") (pin "7") (pinfunction "B_7") (pintype "passive"))
      (node (ref "R83") (pin "1") (pinfunction "1_1") (pintype "passive"))
    )
    (net (code "94") (name "Net-(LED13-A)") (class "Default")
      (node (ref "LED13") (pin "2") (pinfunction "A_2") (pintype "passive"))
      (node (ref "R33") (pin "2") (pinfunction "2_2") (pintype "passive"))
    )
    (net (code "95") (name "Net-(LED14-A)") (class "Default")
      (node (ref "LED14") (pin "2") (pinfunction "A_2") (pintype "passive"))
      (node (ref "R34") (pin "2") (pinfunction "2_2") (pintype "passive"))
    )
    (net (code "96") (name "Net-(LED15-A)") (class "Default")
      (node (ref "LED15") (pin "2") (pinfunction "A_2") (pintype "passive"))
      (node (ref "R47") (pin "1") (pinfunction "1_1") (pintype "passive"))
    )
    (net (code "97") (name "Net-(LED16-A)") (class "Default")
      (node (ref "LED16") (pin "2") (pinfunction "A_2") (pintype "passive"))
      (node (ref "R48") (pin "1") (pinfunction "1_1") (pintype "passive"))
    )
    (net (code "98") (name "Net-(LED17-A)") (class "Default")
      (node (ref "LED17") (pin "2") (pinfunction "A_2") (pintype "passive"))
      (node (ref "R49") (pin "2") (pinfunction "2_2") (pintype "passive"))
    )
    (net (code "99") (name "Net-(LED18-A)") (class "Default")
      (node (ref "LED18") (pin "2") (pinfunction "A_2") (pintype "passive"))
      (node (ref "R50") (pin "2") (pinfunction "2_2") (pintype "passive"))
    )
    (net (code "100") (name "Net-(LED19-A)") (class "Default")
      (node (ref "LED19") (pin "2") (pinfunction "A_2") (pintype "passive"))
      (node (ref "R63") (pin "1") (pinfunction "1_1") (pintype "passive"))
    )
    (net (code "101") (name "Net-(LED20-A)") (class "Default")
      (node (ref "LED20") (pin "2") (pinfunction "A_2") (pintype "passive"))
      (node (ref "R64") (pin "1") (pinfunction "1_1") (pintype "passive"))
    )
    (net (code "102") (name "Net-(LED21-A)") (class "Default")
      (node (ref "LED21") (pin "2") (pinfunction "A_2") (pintype "passive"))
      (node (ref "R65") (pin "2") (pinfunction "2_2") (pintype "passive"))
    )
    (net (code "103") (name "Net-(LED22-A)") (class "Default")
      (node (ref "LED22") (pin "2") (pinfunction "A_2") (pintype "passive"))
      (node (ref "R66") (pin "2") (pinfunction "2_2") (pintype "passive"))
    )
    (net (code "104") (name "Net-(LED23-A)") (class "Default")
      (node (ref "LED23") (pin "2") (pinfunction "A_2") (pintype "passive"))
      (node (ref "R79") (pin "1") (pinfunction "1_1") (pintype "passive"))
    )
    (net (code "105") (name "Net-(LED24-A)") (class "Default")
      (node (ref "LED24") (pin "2") (pinfunction "A_2") (pintype "passive"))
      (node (ref "R80") (pin "1") (pinfunction "1_1") (pintype "passive"))
    )
    (net (code "106") (name "Net-(LED25-A)") (class "Default")
      (node (ref "LED25") (pin "2") (pinfunction "A_2") (pintype "passive"))
      (node (ref "R81") (pin "2") (pinfunction "2_2") (pintype "passive"))
    )
    (net (code "107") (name "Net-(LED26-A)") (class "Default")
      (node (ref "LED26") (pin "2") (pinfunction "A_2") (pintype "passive"))
      (node (ref "R88") (pin "1") (pinfunction "1_1") (pintype "passive"))
    )
  )
)
